# nrfice.net
KiCad netlist of a schematic drawn in EAGLE
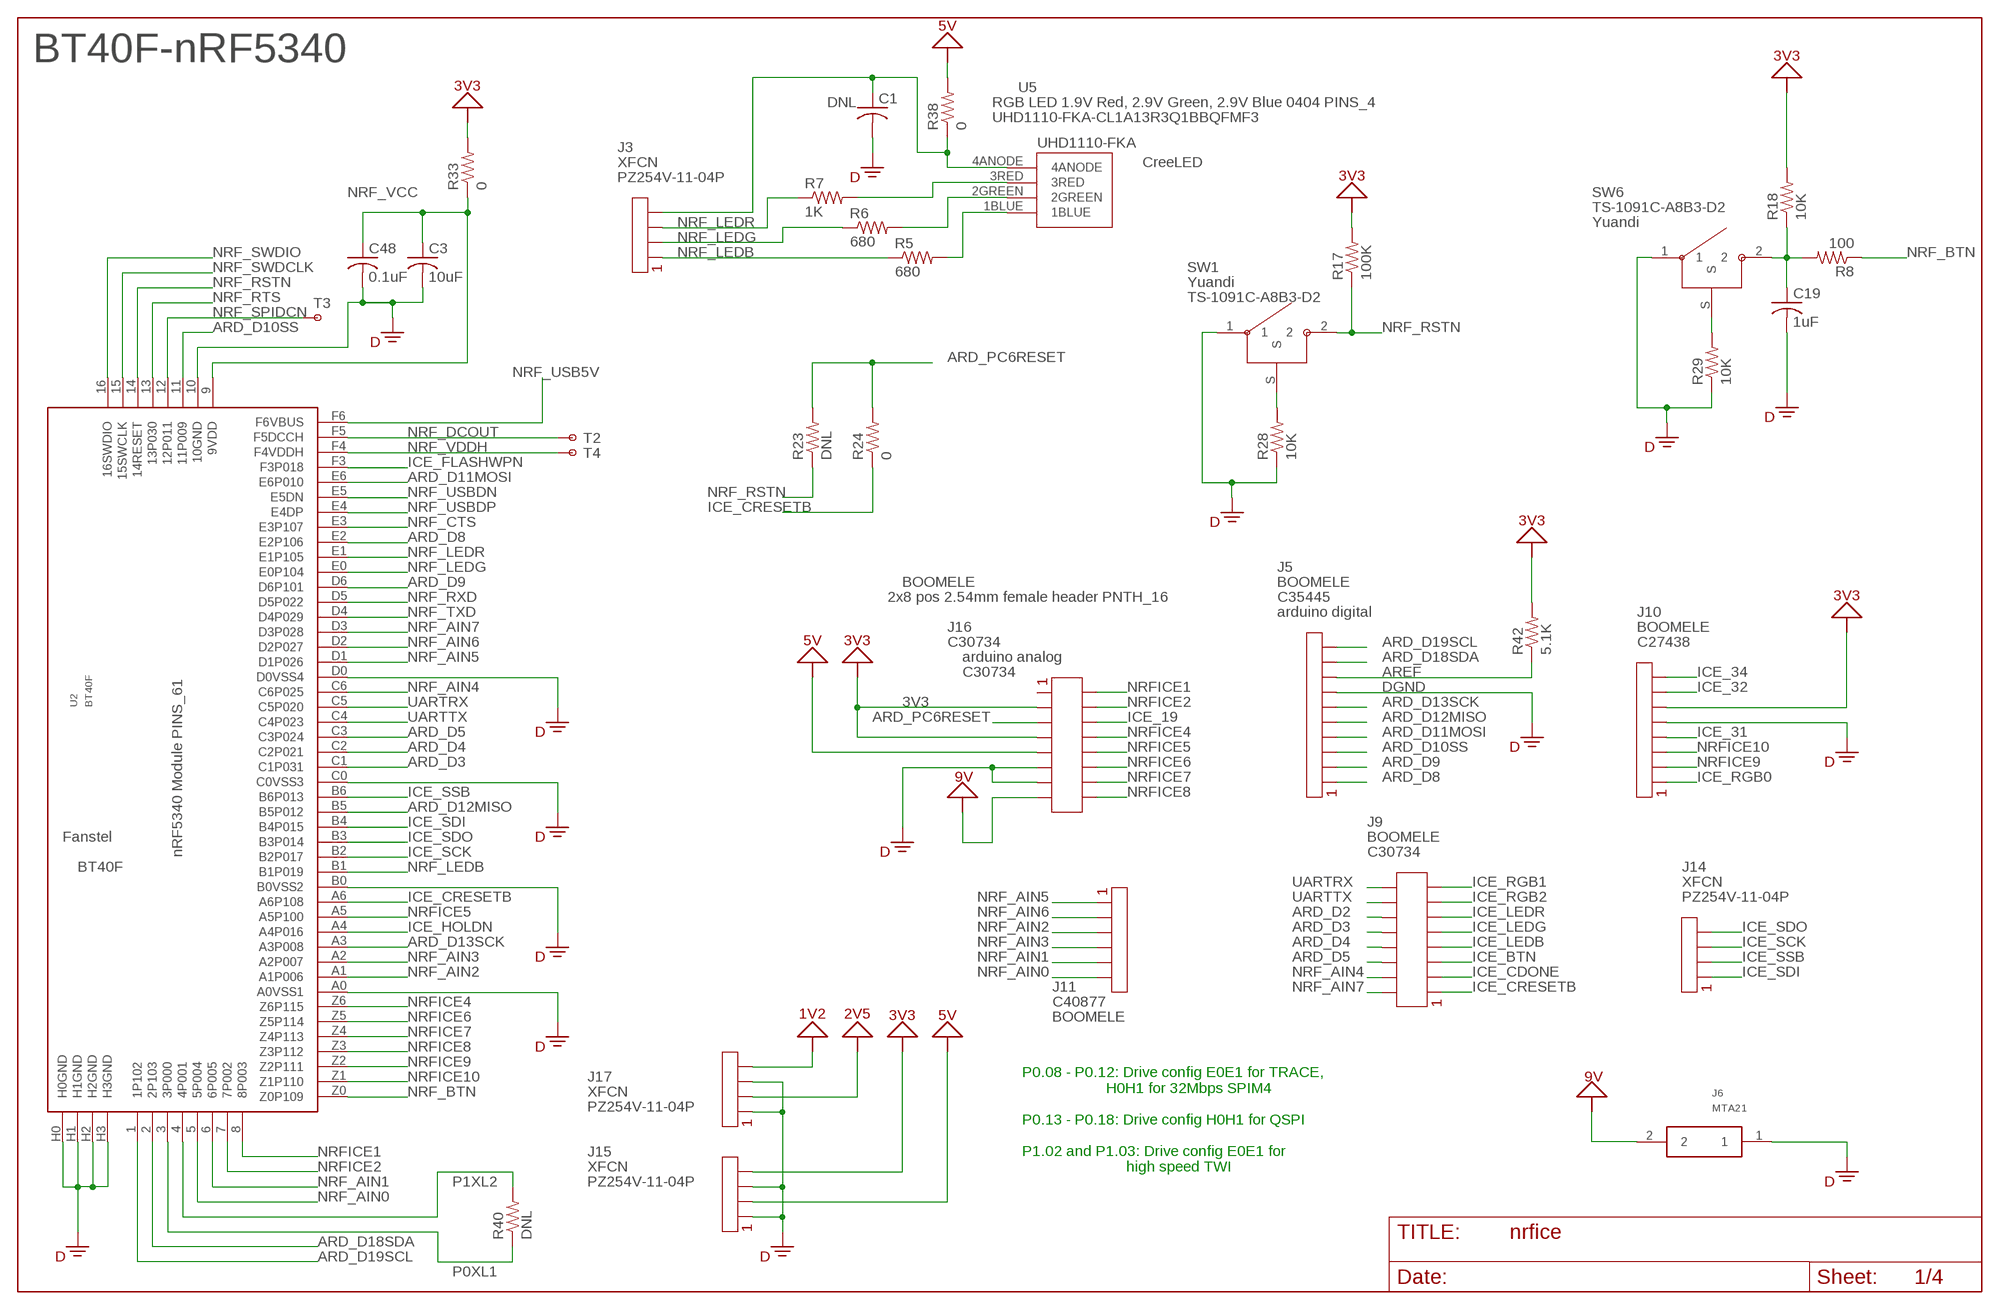
[diagram p0: schematic, sheet 1]
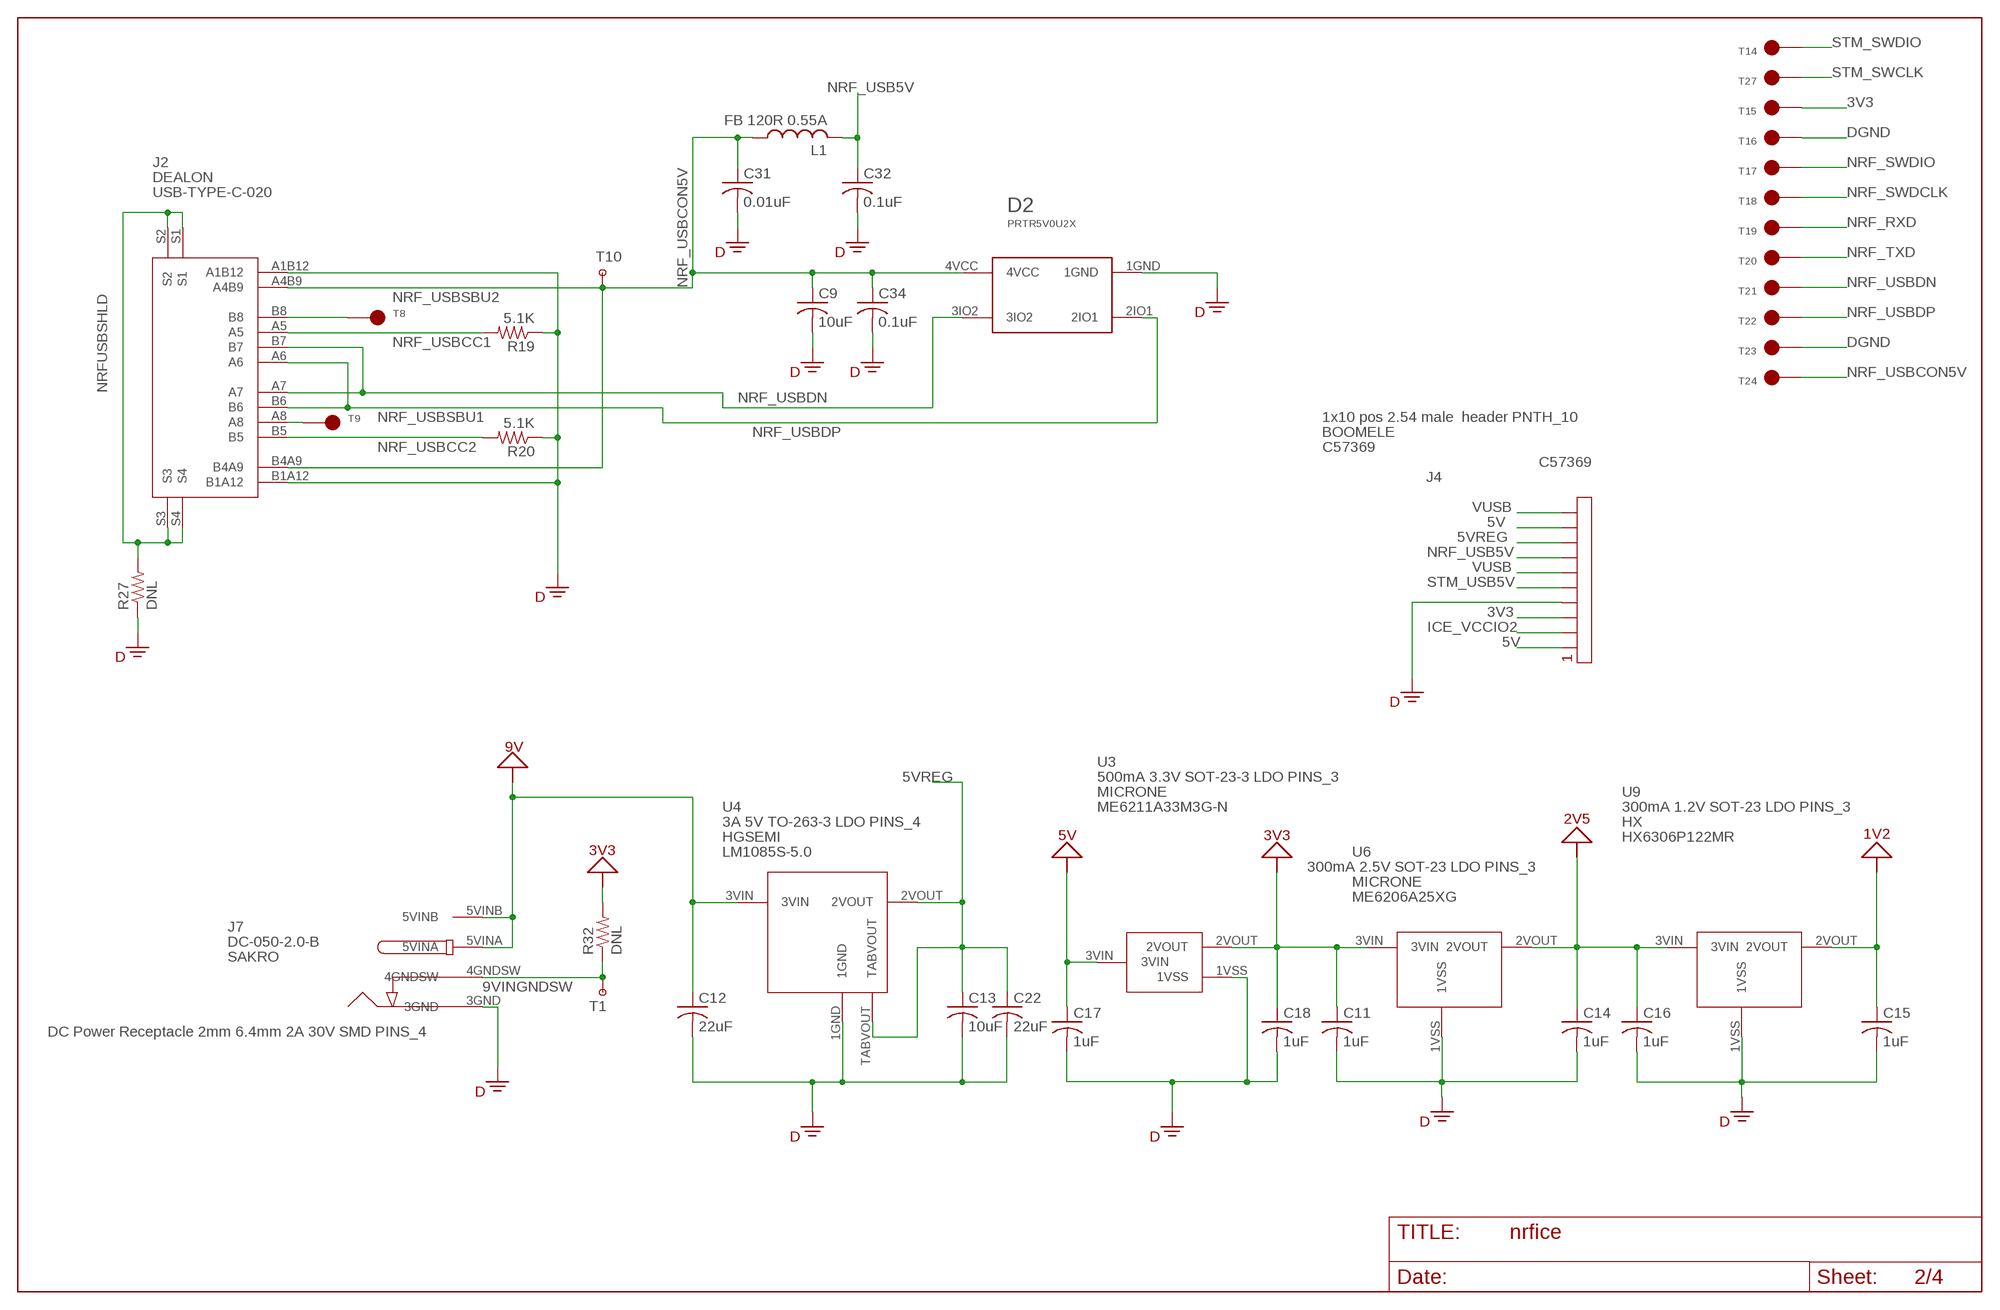
[diagram p1: schematic, sheet 2]
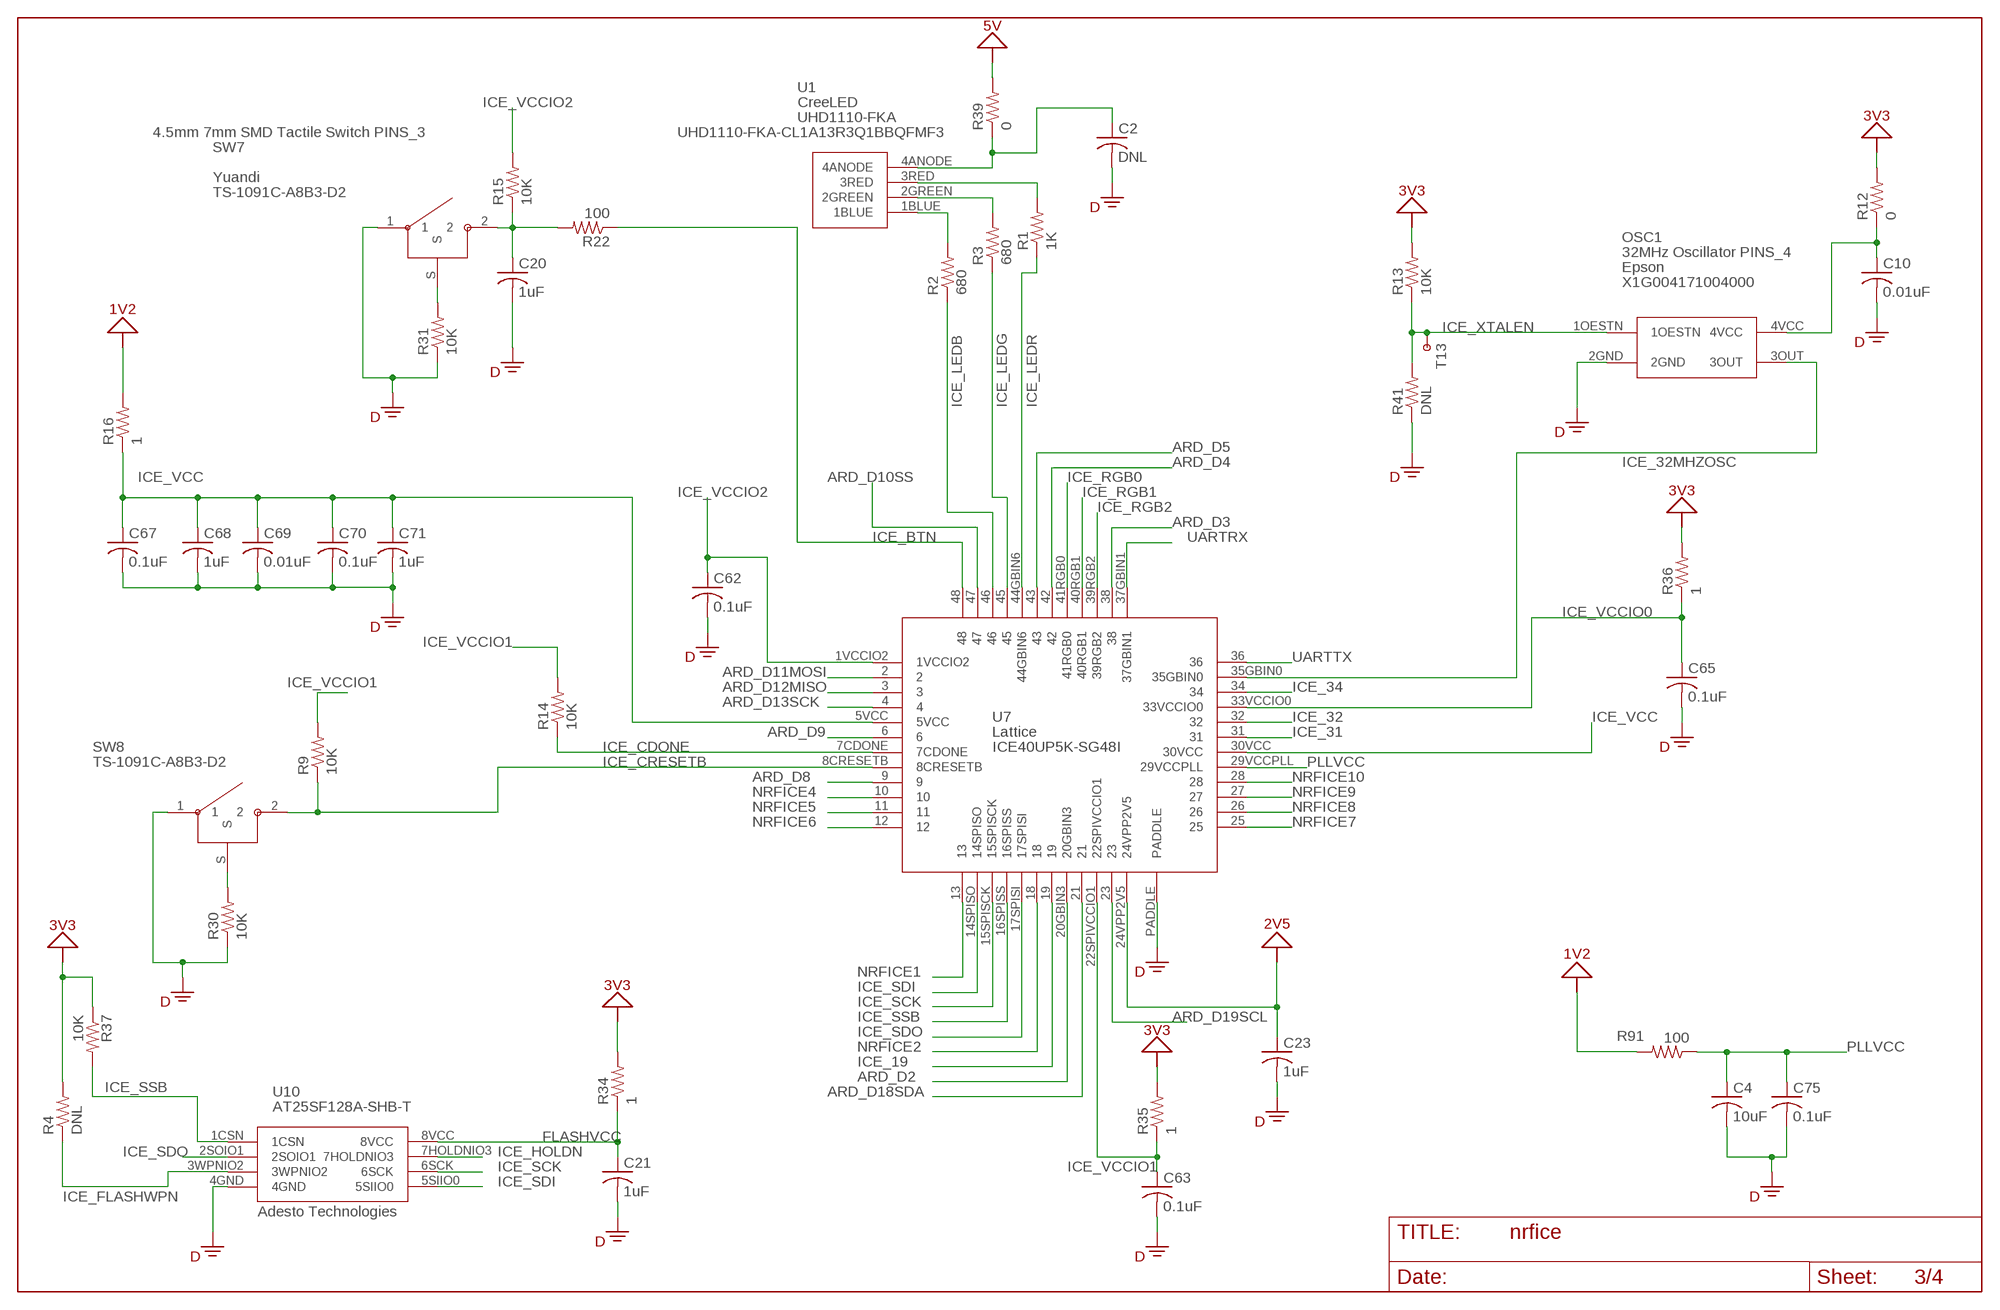
[diagram p2: schematic, sheet 3]
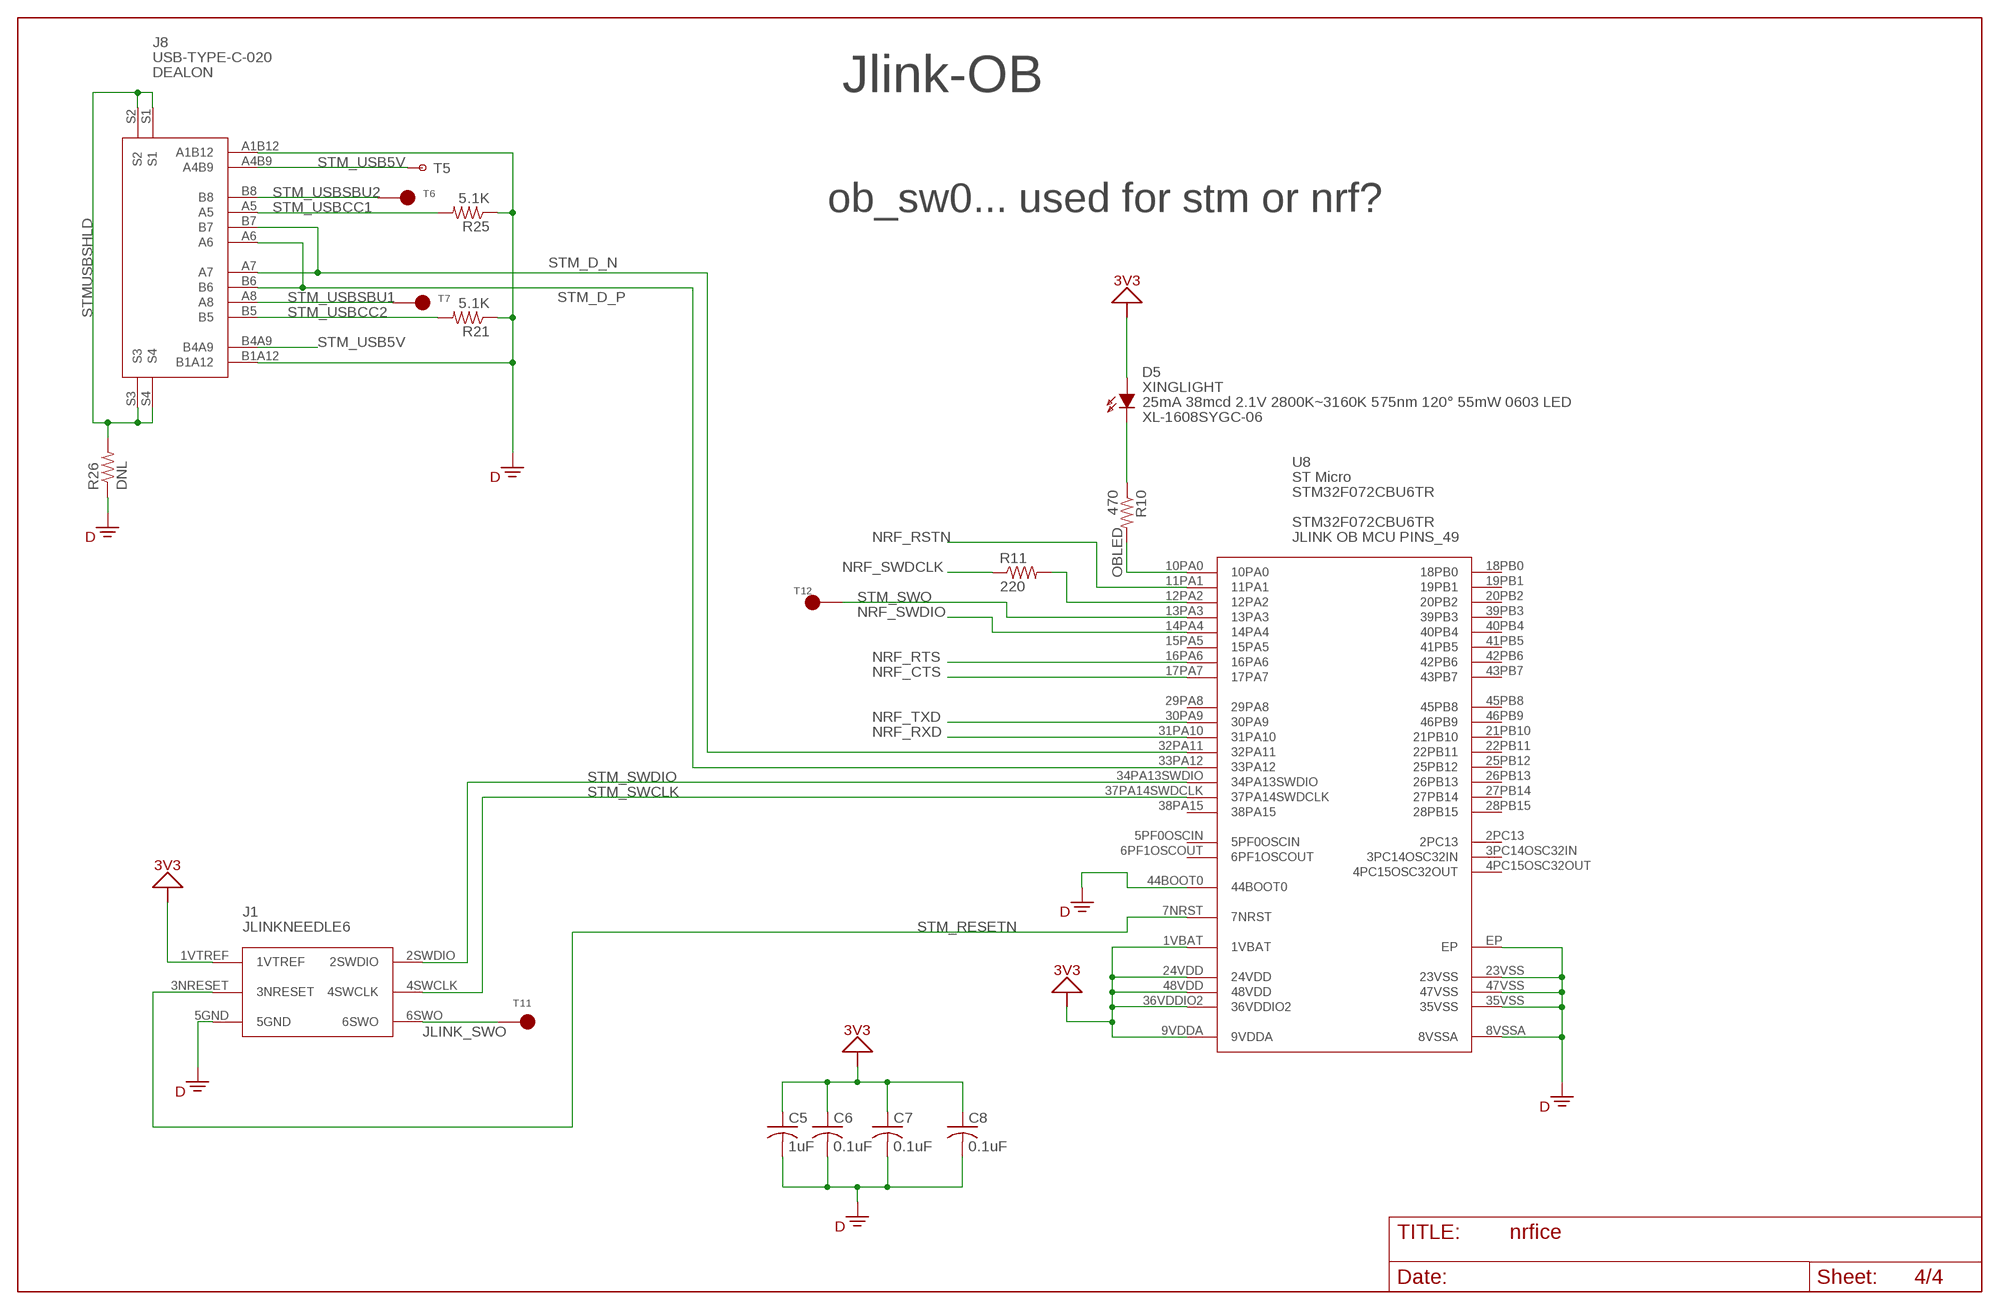
[diagram p3: schematic, sheet 4]

(export (version "E")
  (design (tool "Eeschema 10.0.6"))
  (components
    (comp (ref "C5")
      (value "1uF")
      (footprint "eagle-import:RCL_C0402")
      (fields
        (field (name "DESC") "1uF,10V,10%,X5R,0402")
        (field (name "MAN") "Samsung")
        (field (name "MPN") "CL05A105KP5NNNC")
      )
      (libsource (lib "eagle-import") (part "C-USC0402"))
    )
    (comp (ref "C6")
      (value "0.1uF")
      (footprint "eagle-import:RCL_C0402")
      (fields
        (field (name "DESC") "0.1uF,10V,10%,X7R,0402")
        (field (name "MAN") "KEMET")
        (field (name "MPN") "C0402C104K8RAC7867")
      )
      (libsource (lib "eagle-import") (part "C-USC0402"))
    )
    (comp (ref "C7")
      (value "0.1uF")
      (footprint "eagle-import:RCL_C0402")
      (fields
        (field (name "DESC") "0.1uF,10V,10%,X7R,0402")
        (field (name "MAN") "KEMET")
        (field (name "MPN") "C0402C104K8RAC7867")
      )
      (libsource (lib "eagle-import") (part "C-USC0402"))
    )
    (comp (ref "C8")
      (value "0.1uF")
      (footprint "eagle-import:RCL_C0402")
      (fields
        (field (name "DESC") "0.1uF,10V,10%,X7R,0402")
        (field (name "MAN") "KEMET")
        (field (name "MPN") "C0402C104K8RAC7867")
      )
      (libsource (lib "eagle-import") (part "C-USC0402"))
    )
    (comp (ref "D5")
      (value "XL-1608SYGC-06")
      (footprint "eagle-import:XL-1608SYGC-06")
      (fields
        (field (name "DESC") "25mA 38mcd 2.1V 2800K~3160K 575nm 120° 55mW 0603 LED")
        (field (name "MAN") "XINGLIGHT")
        (field (name "MPN") "XL-1608SYGC-06")
      )
      (libsource (lib "eagle-import") (part "XL-1608SYGC-06"))
    )
    (comp (ref "J1")
      (value "JLINKNEEDLE6")
      (footprint "eagle-import:JLINKNEEDLE6")
      (fields (field (name "DESC") "DNL"))
      (libsource (lib "eagle-import") (part "JLINKNEEDLE6"))
    )
    (comp (ref "J8")
      (value "USB-TYPE-C-020")
      (footprint "eagle-import:USB-TYPE-C-020")
      (fields
        (field (name "DESC") "usb type c connector PINS_12")
        (field (name "MAN") "DEALON")
        (field (name "MPN") "USB-TYPE-C-020")
      )
      (libsource (lib "eagle-import") (part "USB-TYPE-C-020"))
    )
    (comp (ref "R10")
      (value "470")
      (footprint "eagle-import:RCL_R0402")
      (fields
        (field (name "DESC") "470 Ohm,1%,1/16W,0402")
        (field (name "MAN") "YAGEO")
        (field (name "MPN") "RC0402FR-07470RL")
      )
      (libsource (lib "eagle-import") (part "R-US_R0402"))
    )
    (comp (ref "R11")
      (value "220")
      (footprint "eagle-import:RCL_R0402")
      (fields
        (field (name "DESC") "220 Ohm,1%,1/16W,0402")
        (field (name "MAN") "YAGEO")
        (field (name "MPN") "RC0402FR-07220RL")
      )
      (libsource (lib "eagle-import") (part "R-US_R0402"))
    )
    (comp (ref "R21")
      (value "5.1K")
      (footprint "eagle-import:RCL_R0402")
      (fields (field (name "MPN") "RC0402FR-075K1L"))
      (libsource (lib "eagle-import") (part "R-US_R0402"))
    )
    (comp (ref "R25")
      (value "5.1K")
      (footprint "eagle-import:RCL_R0402")
      (fields (field (name "MPN") "RC0402FR-075K1L"))
      (libsource (lib "eagle-import") (part "R-US_R0402"))
    )
    (comp (ref "R26")
      (value "DNL")
      (footprint "eagle-import:RCL_R0402")
      (fields (field (name "DESC") "DNL") (field (name "MAN") "YAGEO") (field (name "MPN") "RC0402FR-0710KL"))
      (libsource (lib "eagle-import") (part "R-US_R0402"))
    )
    (comp (ref "T5")
      (value "MTA1")
      (footprint "eagle-import:MTA1")
      (fields (field (name "DESC") "DNL"))
      (libsource (lib "eagle-import") (part "MTA1"))
    )
    (comp (ref "T6")
      (value "T")
      (footprint "eagle-import:T")
      (fields (field (name "DESC") "DNL"))
      (libsource (lib "eagle-import") (part "T"))
    )
    (comp (ref "T7")
      (value "T")
      (footprint "eagle-import:T")
      (fields (field (name "DESC") "DNL"))
      (libsource (lib "eagle-import") (part "T"))
    )
    (comp (ref "T11")
      (value "T")
      (footprint "eagle-import:T")
      (fields (field (name "DESC") "DNL"))
      (libsource (lib "eagle-import") (part "T"))
    )
    (comp (ref "T12")
      (value "T")
      (footprint "eagle-import:T")
      (fields (field (name "DESC") "DNL"))
      (libsource (lib "eagle-import") (part "T"))
    )
    (comp (ref "U8")
      (value "STM32F072CBU6TR")
      (footprint "eagle-import:STM32F072CBU6TR")
      (fields
        (field (name "DESC") "JLINK OB MCU PINS_49")
        (field (name "MAN") "ST Micro")
        (field (name "MPN") "STM32F072CBU6TR")
      )
      (libsource (lib "eagle-import") (part "STM32F072CBU6TR"))
    )
    (comp (ref "C9")
      (value "10uF")
      (footprint "eagle-import:RCL_C0805")
      (fields
        (field (name "DESC") "10uF,16V,10%,X5R,0805")
        (field (name "MAN") "Samsung")
        (field (name "MPN") "CL21A106KOQNNNE")
      )
      (libsource (lib "eagle-import") (part "C-USC0805"))
    )
    (comp (ref "C11")
      (value "1uF")
      (footprint "eagle-import:RCL_C0402")
      (fields
        (field (name "DESC") "1uF,10V,10%,X5R,0402")
        (field (name "MAN") "Samsung")
        (field (name "MPN") "CL05A105KP5NNNC")
      )
      (libsource (lib "eagle-import") (part "C-USC0402"))
    )
    (comp (ref "C12")
      (value "22uF")
      (footprint "eagle-import:RCL_C0805")
      (fields
        (field (name "DESC") "22uF,25V,20%,X5R,0805")
        (field (name "MAN") "Samsung")
        (field (name "MPN") "CL21A226MAYNNNE")
      )
      (libsource (lib "eagle-import") (part "C-USC0805"))
    )
    (comp (ref "C13")
      (value "10uF")
      (footprint "eagle-import:RCL_C0805")
      (fields
        (field (name "DESC") "10uF,16V,10%,X5R,0805")
        (field (name "MAN") "Samsung")
        (field (name "MPN") "CL21A106KOQNNNE")
      )
      (libsource (lib "eagle-import") (part "C-USC0805"))
    )
    (comp (ref "C14")
      (value "1uF")
      (footprint "eagle-import:RCL_C0402")
      (fields
        (field (name "DESC") "1uF,10V,10%,X5R,0402")
        (field (name "MAN") "Samsung")
        (field (name "MPN") "CL05A105KP5NNNC")
      )
      (libsource (lib "eagle-import") (part "C-USC0402"))
    )
    (comp (ref "C15")
      (value "1uF")
      (footprint "eagle-import:RCL_C0402")
      (fields
        (field (name "DESC") "1uF,10V,10%,X5R,0402")
        (field (name "MAN") "Samsung")
        (field (name "MPN") "CL05A105KP5NNNC")
      )
      (libsource (lib "eagle-import") (part "C-USC0402"))
    )
    (comp (ref "C16")
      (value "1uF")
      (footprint "eagle-import:RCL_C0402")
      (fields
        (field (name "DESC") "1uF,10V,10%,X5R,0402")
        (field (name "MAN") "Samsung")
        (field (name "MPN") "CL05A105KP5NNNC")
      )
      (libsource (lib "eagle-import") (part "C-USC0402"))
    )
    (comp (ref "C17")
      (value "1uF")
      (footprint "eagle-import:RCL_C0402")
      (fields
        (field (name "DESC") "1uF,10V,10%,X5R,0402")
        (field (name "MAN") "Samsung")
        (field (name "MPN") "CL05A105KP5NNNC")
      )
      (libsource (lib "eagle-import") (part "C-USC0402"))
    )
    (comp (ref "C18")
      (value "1uF")
      (footprint "eagle-import:RCL_C0402")
      (fields
        (field (name "DESC") "1uF,10V,10%,X5R,0402")
        (field (name "MAN") "Samsung")
        (field (name "MPN") "CL05A105KP5NNNC")
      )
      (libsource (lib "eagle-import") (part "C-USC0402"))
    )
    (comp (ref "C22")
      (value "22uF")
      (footprint "eagle-import:RCL_C0805")
      (fields
        (field (name "DESC") "22uF,25V,20%,X5R,0805")
        (field (name "MAN") "Samsung")
        (field (name "MPN") "CL21A226MAYNNNE")
      )
      (libsource (lib "eagle-import") (part "C-USC0805"))
    )
    (comp (ref "C31")
      (value "0.01uF")
      (footprint "eagle-import:RCL_C0402")
      (fields (field (name "MPN") "C0402C103J4RAC"))
      (libsource (lib "eagle-import") (part "C-USC0402"))
    )
    (comp (ref "C32")
      (value "0.1uF")
      (footprint "eagle-import:RCL_C0402")
      (fields (field (name "MPN") "C0402C104K8RAC7867"))
      (libsource (lib "eagle-import") (part "C-USC0402"))
    )
    (comp (ref "C34")
      (value "0.1uF")
      (footprint "eagle-import:RCL_C0402")
      (fields (field (name "MPN") "C0402C104K8RAC7867"))
      (libsource (lib "eagle-import") (part "C-USC0402"))
    )
    (comp (ref "D2")
      (value "PRTR5V0U2X")
      (footprint "eagle-import:PRTR5V0U2X")
      (fields (field (name "MAN") "Nexperia") (field (name "MPN") "PRTR5V0U2X"))
      (libsource (lib "eagle-import") (part "PRTR5V0U2X"))
    )
    (comp (ref "J2")
      (value "USB-TYPE-C-020")
      (footprint "eagle-import:USB-TYPE-C-020")
      (fields
        (field (name "DESC") "usb type c connector PINS_12")
        (field (name "MAN") "DEALON")
        (field (name "MPN") "USB-TYPE-C-020")
      )
      (libsource (lib "eagle-import") (part "USB-TYPE-C-020"))
    )
    (comp (ref "J4")
      (value "C57369")
      (footprint "eagle-import:C57369")
      (fields
        (field (name "DESC") "1x10 pos 2.54 male  header PNTH_10")
        (field (name "MAN") "BOOMELE")
        (field (name "MPN") "C57369")
      )
      (libsource (lib "eagle-import") (part "C57369"))
    )
    (comp (ref "J7")
      (value "DC-050-2.0-B")
      (footprint "eagle-import:DC-050-2.0-B")
      (fields
        (field (name "DESC") "DC Power Receptacle 2mm 6.4mm 2A 30V SMD PINS_4")
        (field (name "MAN") "SAKRO")
        (field (name "MPN") "DC-050-2.0-B")
      )
      (libsource (lib "eagle-import") (part "DC-050-2.0-B"))
    )
    (comp (ref "L1")
      (value "FB 120R 0.55A")
      (footprint "eagle-import:L0402")
      (fields (field (name "MPN") "BLM15AG121SN1D"))
      (libsource (lib "eagle-import") (part "L-USL0402"))
    )
    (comp (ref "R19")
      (value "5.1K")
      (footprint "eagle-import:RCL_R0402")
      (fields (field (name "MPN") "RC0402FR-075K1L"))
      (libsource (lib "eagle-import") (part "R-US_R0402"))
    )
    (comp (ref "R20")
      (value "5.1K")
      (footprint "eagle-import:RCL_R0402")
      (fields (field (name "MPN") "RC0402FR-075K1L"))
      (libsource (lib "eagle-import") (part "R-US_R0402"))
    )
    (comp (ref "R27")
      (value "DNL")
      (footprint "eagle-import:RCL_R0402")
      (fields (field (name "MPN") "RC0402FR-0710KL"))
      (libsource (lib "eagle-import") (part "R-US_R0402"))
    )
    (comp (ref "R32")
      (value "DNL")
      (footprint "eagle-import:RCL_R0402")
      (fields (field (name "MPN") "RC0402FR-0710KL"))
      (libsource (lib "eagle-import") (part "R-US_R0402"))
    )
    (comp (ref "T1")
      (value "MTA1")
      (footprint "eagle-import:MTA1")
      (fields (field (name "DESC") "DNL"))
      (libsource (lib "eagle-import") (part "MTA1"))
    )
    (comp (ref "T8")
      (value "T")
      (footprint "eagle-import:T")
      (fields (field (name "DESC") "DNL"))
      (libsource (lib "eagle-import") (part "T"))
    )
    (comp (ref "T9")
      (value "T")
      (footprint "eagle-import:T")
      (fields (field (name "DESC") "DNL"))
      (libsource (lib "eagle-import") (part "T"))
    )
    (comp (ref "T10")
      (value "MTA1")
      (footprint "eagle-import:MTA1")
      (fields (field (name "DESC") "DNL"))
      (libsource (lib "eagle-import") (part "MTA1"))
    )
    (comp (ref "T14")
      (value "TT2")
      (footprint "eagle-import:T2")
      (libsource (lib "eagle-import") (part "TT2"))
    )
    (comp (ref "T15")
      (value "TT2")
      (footprint "eagle-import:T2")
      (libsource (lib "eagle-import") (part "TT2"))
    )
    (comp (ref "T16")
      (value "TT2")
      (footprint "eagle-import:T2")
      (libsource (lib "eagle-import") (part "TT2"))
    )
    (comp (ref "T17")
      (value "TT2")
      (footprint "eagle-import:T2")
      (libsource (lib "eagle-import") (part "TT2"))
    )
    (comp (ref "T18")
      (value "TT2")
      (footprint "eagle-import:T2")
      (libsource (lib "eagle-import") (part "TT2"))
    )
    (comp (ref "T19")
      (value "TT2")
      (footprint "eagle-import:T2")
      (libsource (lib "eagle-import") (part "TT2"))
    )
    (comp (ref "T20")
      (value "TT2")
      (footprint "eagle-import:T2")
      (libsource (lib "eagle-import") (part "TT2"))
    )
    (comp (ref "T21")
      (value "TT2")
      (footprint "eagle-import:T2")
      (libsource (lib "eagle-import") (part "TT2"))
    )
    (comp (ref "T22")
      (value "TT2")
      (footprint "eagle-import:T2")
      (libsource (lib "eagle-import") (part "TT2"))
    )
    (comp (ref "T23")
      (value "TT2")
      (footprint "eagle-import:T2")
      (libsource (lib "eagle-import") (part "TT2"))
    )
    (comp (ref "T24")
      (value "TT2")
      (footprint "eagle-import:T2")
      (libsource (lib "eagle-import") (part "TT2"))
    )
    (comp (ref "T27")
      (value "TT2")
      (footprint "eagle-import:T2")
      (libsource (lib "eagle-import") (part "TT2"))
    )
    (comp (ref "U3")
      (value "ME6211A33M3G-N")
      (footprint "eagle-import:ME6211A33M3G-N")
      (fields
        (field (name "DESC") "500mA 3.3V SOT-23-3 LDO PINS_3")
        (field (name "MAN") "MICRONE")
        (field (name "MPN") "ME6211A33M3G-N")
      )
      (libsource (lib "eagle-import") (part "ME6211A33M3G-N"))
    )
    (comp (ref "U4")
      (value "LM1085S-5.0")
      (footprint "eagle-import:LM1085S-5.0")
      (fields
        (field (name "DESC") "3A 5V TO-263-3 LDO PINS_4")
        (field (name "MAN") "HGSEMI")
        (field (name "MPN") "LM1085S-5.0")
      )
      (libsource (lib "eagle-import") (part "LM1085S-5.0"))
    )
    (comp (ref "U6")
      (value "ME6206A25XG")
      (footprint "eagle-import:ME6206A25XG")
      (fields
        (field (name "DESC") "300mA 2.5V SOT-23 LDO PINS_3")
        (field (name "MAN") "MICRONE")
        (field (name "MPN") "ME6206A25XG")
      )
      (libsource (lib "eagle-import") (part "ME6206A25XG"))
    )
    (comp (ref "U9")
      (value "HX6306P122MR")
      (footprint "eagle-import:HX6306P122MR")
      (fields
        (field (name "DESC") "300mA 1.2V SOT-23 LDO PINS_3")
        (field (name "MAN") "HX")
        (field (name "MPN") "HX6306P122MR")
      )
      (libsource (lib "eagle-import") (part "HX6306P122MR"))
    )
    (comp (ref "C2")
      (value "DNL")
      (footprint "eagle-import:RCL_C0402")
      (fields (field (name "MPN") "CL05A105KP5NNNC"))
      (libsource (lib "eagle-import") (part "C-USC0402"))
    )
    (comp (ref "C4")
      (value "10uF")
      (footprint "eagle-import:RCL_C0805")
      (fields
        (field (name "DESC") "10uF,16V,10%,X5R,0805")
        (field (name "MAN") "Samsung")
        (field (name "MPN") "CL21A106KOQNNNE")
      )
      (libsource (lib "eagle-import") (part "C-USC0805"))
    )
    (comp (ref "C10")
      (value "0.01uF")
      (footprint "eagle-import:RCL_C0402")
      (fields
        (field (name "DESC") "0.01uF,16V,5%,X7R,0402")
        (field (name "MAN") "KEMET")
        (field (name "MPN") "C0402C103J4RAC")
      )
      (libsource (lib "eagle-import") (part "C-USC0402"))
    )
    (comp (ref "C20")
      (value "1uF")
      (footprint "eagle-import:RCL_C0402")
      (fields (field (name "MPN") "CL05A105KP5NNNC"))
      (libsource (lib "eagle-import") (part "C-USC0402"))
    )
    (comp (ref "C21")
      (value "1uF")
      (footprint "eagle-import:RCL_C0402")
      (fields (field (name "MPN") "CL05A105KP5NNNC"))
      (libsource (lib "eagle-import") (part "C-USC0402"))
    )
    (comp (ref "C23")
      (value "1uF")
      (footprint "eagle-import:RCL_C0402")
      (fields
        (field (name "DESC") "1uF,10V,10%,X5R,0402")
        (field (name "MAN") "Samsung")
        (field (name "MPN") "CL05A105KP5NNNC")
      )
      (libsource (lib "eagle-import") (part "C-USC0402"))
    )
    (comp (ref "C62")
      (value "0.1uF")
      (footprint "eagle-import:RCL_C0402")
      (fields
        (field (name "DESC") "0.1uF,10V,10%,X7R,0402")
        (field (name "MAN") "KEMET")
        (field (name "MPN") "C0402C104K8RAC7867")
      )
      (libsource (lib "eagle-import") (part "C-USC0402"))
    )
    (comp (ref "C63")
      (value "0.1uF")
      (footprint "eagle-import:RCL_C0402")
      (fields
        (field (name "DESC") "0.1uF,10V,10%,X7R,0402")
        (field (name "MAN") "KEMET")
        (field (name "MPN") "C0402C104K8RAC7867")
      )
      (libsource (lib "eagle-import") (part "C-USC0402"))
    )
    (comp (ref "C65")
      (value "0.1uF")
      (footprint "eagle-import:RCL_C0402")
      (fields
        (field (name "DESC") "0.1uF,10V,10%,X7R,0402")
        (field (name "MAN") "KEMET")
        (field (name "MPN") "C0402C104K8RAC7867")
      )
      (libsource (lib "eagle-import") (part "C-USC0402"))
    )
    (comp (ref "C67")
      (value "0.1uF")
      (footprint "eagle-import:RCL_C0402")
      (fields
        (field (name "DESC") "0.1uF,10V,10%,X7R,0402")
        (field (name "MAN") "KEMET")
        (field (name "MPN") "C0402C104K8RAC7867")
      )
      (libsource (lib "eagle-import") (part "C-USC0402"))
    )
    (comp (ref "C68")
      (value "1uF")
      (footprint "eagle-import:RCL_C0402")
      (fields
        (field (name "DESC") "1uF,10V,10%,X5R,0402")
        (field (name "MAN") "Samsung")
        (field (name "MPN") "CL05A105KP5NNNC")
      )
      (libsource (lib "eagle-import") (part "C-USC0402"))
    )
    (comp (ref "C69")
      (value "0.01uF")
      (footprint "eagle-import:RCL_C0402")
      (fields
        (field (name "DESC") "0.01uF,16V,5%,X7R,0402")
        (field (name "MAN") "KEMET")
        (field (name "MPN") "C0402C103J4RAC")
      )
      (libsource (lib "eagle-import") (part "C-USC0402"))
    )
    (comp (ref "C70")
      (value "0.1uF")
      (footprint "eagle-import:RCL_C0402")
      (fields
        (field (name "DESC") "0.1uF,10V,10%,X7R,0402")
        (field (name "MAN") "KEMET")
        (field (name "MPN") "C0402C104K8RAC7867")
      )
      (libsource (lib "eagle-import") (part "C-USC0402"))
    )
    (comp (ref "C71")
      (value "1uF")
      (footprint "eagle-import:RCL_C0402")
      (fields
        (field (name "DESC") "1uF,10V,10%,X5R,0402")
        (field (name "MAN") "Samsung")
        (field (name "MPN") "CL05A105KP5NNNC")
      )
      (libsource (lib "eagle-import") (part "C-USC0402"))
    )
    (comp (ref "C75")
      (value "0.1uF")
      (footprint "eagle-import:RCL_C0402")
      (fields
        (field (name "DESC") "0.1uF,10V,10%,X7R,0402")
        (field (name "MAN") "KEMET")
        (field (name "MPN") "C0402C104K8RAC7867")
      )
      (libsource (lib "eagle-import") (part "C-USC0402"))
    )
    (comp (ref "OSC1")
      (value "X1G004171004000")
      (footprint "eagle-import:X1G004171004000")
      (fields
        (field (name "DESC") "32MHz Oscillator PINS_4")
        (field (name "MAN") "Epson")
        (field (name "MPN") "X1G004171004000")
      )
      (libsource (lib "eagle-import") (part "X1G004171004000"))
    )
    (comp (ref "R1")
      (value "1K")
      (footprint "eagle-import:RCL_R0402")
      (fields (field (name "MPN") "RC0402FR-071KL"))
      (libsource (lib "eagle-import") (part "R-US_R0402"))
    )
    (comp (ref "R2")
      (value "680")
      (footprint "eagle-import:RCL_R0402")
      (fields (field (name "MPN") "RC0402FR-07680RL"))
      (libsource (lib "eagle-import") (part "R-US_R0402"))
    )
    (comp (ref "R3")
      (value "680")
      (footprint "eagle-import:RCL_R0402")
      (fields (field (name "MPN") "RC0402FR-07680RL"))
      (libsource (lib "eagle-import") (part "R-US_R0402"))
    )
    (comp (ref "R4")
      (value "DNL")
      (footprint "eagle-import:RCL_R0402")
      (fields (field (name "DESC") "DNL") (field (name "MAN") "YAGEO") (field (name "MPN") "RC0402FR-0710KL"))
      (libsource (lib "eagle-import") (part "R-US_R0402"))
    )
    (comp (ref "R9")
      (value "10K")
      (footprint "eagle-import:RCL_R0402")
      (fields
        (field (name "DESC") "10K Ohm,1%,1/16W,0402")
        (field (name "MAN") "YAGEO")
        (field (name "MPN") "RC0402FR-0710KL")
      )
      (libsource (lib "eagle-import") (part "R-US_R0402"))
    )
    (comp (ref "R12")
      (value "0")
      (footprint "eagle-import:RCL_R0603")
      (fields
        (field (name "DESC") "0 Ohm,1%,1/10W,0603")
        (field (name "MAN") "YAGEO")
        (field (name "MPN") "RC0603FR-070RL")
      )
      (libsource (lib "eagle-import") (part "R-US_R0603"))
    )
    (comp (ref "R13")
      (value "10K")
      (footprint "eagle-import:RCL_R0402")
      (fields
        (field (name "DESC") "10K Ohm,1%,1/16W,0402")
        (field (name "MAN") "YAGEO")
        (field (name "MPN") "RC0402FR-0710KL")
      )
      (libsource (lib "eagle-import") (part "R-US_R0402"))
    )
    (comp (ref "R14")
      (value "10K")
      (footprint "eagle-import:RCL_R0402")
      (fields
        (field (name "DESC") "10K Ohm,1%,1/16W,0402")
        (field (name "MAN") "YAGEO")
        (field (name "MPN") "RC0402FR-0710KL")
      )
      (libsource (lib "eagle-import") (part "R-US_R0402"))
    )
    (comp (ref "R15")
      (value "10K")
      (footprint "eagle-import:RCL_R0402")
      (fields
        (field (name "DESC") "10K Ohm,1%,1/16W,0402")
        (field (name "MAN") "YAGEO")
        (field (name "MPN") "RC0402FR-0710KL")
      )
      (libsource (lib "eagle-import") (part "R-US_R0402"))
    )
    (comp (ref "R16")
      (value "1")
      (footprint "eagle-import:RCL_R0603")
      (fields
        (field (name "DESC") "1 Ohm,1%,1/10W,0603")
        (field (name "MAN") "YAGEO")
        (field (name "MPN") "RC0603FR-071RL")
      )
      (libsource (lib "eagle-import") (part "R-US_R0603"))
    )
    (comp (ref "R22")
      (value "100")
      (footprint "eagle-import:RCL_R0402")
      (fields
        (field (name "DESC") "100 Ohm,1%,1/16W,0402")
        (field (name "MAN") "YAGEO")
        (field (name "MPN") "RC0402FR-07100RL")
      )
      (libsource (lib "eagle-import") (part "R-US_R0402"))
    )
    (comp (ref "R30")
      (value "10K")
      (footprint "eagle-import:RCL_R0402")
      (fields
        (field (name "DESC") "10K Ohm,1%,1/16W,0402")
        (field (name "MAN") "YAGEO")
        (field (name "MPN") "RC0402FR-0710KL")
      )
      (libsource (lib "eagle-import") (part "R-US_R0402"))
    )
    (comp (ref "R31")
      (value "10K")
      (footprint "eagle-import:RCL_R0402")
      (fields
        (field (name "DESC") "10K Ohm,1%,1/16W,0402")
        (field (name "MAN") "YAGEO")
        (field (name "MPN") "RC0402FR-0710KL")
      )
      (libsource (lib "eagle-import") (part "R-US_R0402"))
    )
    (comp (ref "R34")
      (value "1")
      (footprint "eagle-import:RCL_R0603")
      (fields
        (field (name "DESC") "1 Ohm,1%,1/10W,0603")
        (field (name "MAN") "YAGEO")
        (field (name "MPN") "RC0603FR-071RL")
      )
      (libsource (lib "eagle-import") (part "R-US_R0603"))
    )
    (comp (ref "R35")
      (value "1")
      (footprint "eagle-import:RCL_R0603")
      (fields
        (field (name "DESC") "1 Ohm,1%,1/10W,0603")
        (field (name "MAN") "YAGEO")
        (field (name "MPN") "RC0603FR-071RL")
      )
      (libsource (lib "eagle-import") (part "R-US_R0603"))
    )
    (comp (ref "R36")
      (value "1")
      (footprint "eagle-import:RCL_R0603")
      (fields
        (field (name "DESC") "1 Ohm,1%,1/10W,0603")
        (field (name "MAN") "YAGEO")
        (field (name "MPN") "RC0603FR-071RL")
      )
      (libsource (lib "eagle-import") (part "R-US_R0603"))
    )
    (comp (ref "R37")
      (value "10K")
      (footprint "eagle-import:RCL_R0402")
      (fields
        (field (name "DESC") "10K Ohm,1%,1/16W,0402")
        (field (name "MAN") "YAGEO")
        (field (name "MPN") "RC0402FR-0710KL")
      )
      (libsource (lib "eagle-import") (part "R-US_R0402"))
    )
    (comp (ref "R39")
      (value "0")
      (footprint "eagle-import:RCL_R0402")
      (fields
        (field (name "DESC") "0 Ohm,1%,1/16W,0402")
        (field (name "MAN") "YAGEO")
        (field (name "MPN") "RC0402FR-070RL")
      )
      (libsource (lib "eagle-import") (part "R-US_R0402"))
    )
    (comp (ref "R41")
      (value "DNL")
      (footprint "eagle-import:RCL_R0402")
      (fields (field (name "DESC") "DNL") (field (name "MAN") "YAGEO") (field (name "MPN") "RC0402FR-0710KL"))
      (libsource (lib "eagle-import") (part "R-US_R0402"))
    )
    (comp (ref "R91")
      (value "100")
      (footprint "eagle-import:RCL_R0402")
      (fields
        (field (name "DESC") "100 Ohm,1%,1/16W,0402")
        (field (name "MAN") "YAGEO")
        (field (name "MPN") "RC0402FR-07100RL")
      )
      (libsource (lib "eagle-import") (part "R-US_R0402"))
    )
    (comp (ref "SW7")
      (value "TS-1091C-A8B3-D2")
      (footprint "eagle-import:TS-1091C-A8B3-D2")
      (fields
        (field (name "DESC") "4.5mm 7mm SMD Tactile Switch PINS_3")
        (field (name "MAN") "Yuandi")
        (field (name "MPN") "TS-1091C-A8B3-D2")
      )
      (libsource (lib "eagle-import") (part "TS-1091C-A8B3-D2"))
    )
    (comp (ref "SW8")
      (value "TS-1091C-A8B3-D2")
      (footprint "eagle-import:TS-1091C-A8B3-D2")
      (fields
        (field (name "DESC") "4.5mm 7mm SMD Tactile Switch PINS_3")
        (field (name "MAN") "Yuandi")
        (field (name "MPN") "TS-1091C-A8B3-D2")
      )
      (libsource (lib "eagle-import") (part "TS-1091C-A8B3-D2"))
    )
    (comp (ref "T13")
      (value "MTA1")
      (footprint "eagle-import:MTA1")
      (fields (field (name "DESC") "DNL"))
      (libsource (lib "eagle-import") (part "MTA1"))
    )
    (comp (ref "U1")
      (value "UHD1110-FKA")
      (footprint "eagle-import:UHD1110-FKA")
      (fields
        (field (name "DESC") "RGB LED 1.9V Red, 2.9V Green, 2.9V Blue 0404 PINS_4")
        (field (name "MAN") "CreeLED")
        (field (name "MPN") "UHD1110-FKA-CL1A13R3Q1BBQFMF3")
      )
      (libsource (lib "eagle-import") (part "UHD1110-FKA"))
    )
    (comp (ref "U7")
      (value "ICE40UP5K-SG48I")
      (footprint "eagle-import:ICE40UP5K-SG48I")
      (fields
        (field (name "DESC") "FPGA 48-VFQFN PINS_48")
        (field (name "MAN") "Lattice")
        (field (name "MPN") "ICE40UP5K-SG48I")
      )
      (libsource (lib "eagle-import") (part "ICE40UP5K-SG48I"))
    )
    (comp (ref "U10")
      (value "AT25SF128A-SHB-T")
      (footprint "eagle-import:AT25SF128A-SHB-T")
      (fields
        (field (name "DESC") "NOR Flash 128 Mbit,2.7V to 3.6V,SOIC-W 208mil PINS_8")
        (field (name "MAN") "Adesto Technologies")
        (field (name "MPN") "AT25SF128A-SHB-T")
      )
      (libsource (lib "eagle-import") (part "AT25SF128A-SHB-T"))
    )
    (comp (ref "C1")
      (value "DNL")
      (footprint "eagle-import:RCL_C0402")
      (fields (field (name "DESC") "DNL") (field (name "MPN") "CL05A105KP5NNNC"))
      (libsource (lib "eagle-import") (part "C-USC0402"))
    )
    (comp (ref "C3")
      (value "10uF")
      (footprint "eagle-import:RCL_C0805")
      (fields
        (field (name "DESC") "10uF,16V,10%,X5R,0805")
        (field (name "MAN") "Samsung")
        (field (name "MPN") "CL21A106KOQNNNE")
      )
      (libsource (lib "eagle-import") (part "C-USC0805"))
    )
    (comp (ref "C19")
      (value "1uF")
      (footprint "eagle-import:RCL_C0402")
      (fields (field (name "MPN") "CL05A105KP5NNNC"))
      (libsource (lib "eagle-import") (part "C-USC0402"))
    )
    (comp (ref "C48")
      (value "0.1uF")
      (footprint "eagle-import:RCL_C0402")
      (fields (field (name "MPN") "C0402C104K8RAC7867"))
      (libsource (lib "eagle-import") (part "C-USC0402"))
    )
    (comp (ref "J3")
      (value "PZ254V-11-04P")
      (footprint "eagle-import:PZ254V-11-04P")
      (fields
        (field (name "DESC") "1x4 pos 2.54 male  header PNTH_4")
        (field (name "MAN") "XFCN")
        (field (name "MPN") "PZ254V-11-04P")
      )
      (libsource (lib "eagle-import") (part "PZ254V-11-04P"))
    )
    (comp (ref "J5")
      (value "C35445")
      (footprint "eagle-import:C35445")
      (fields
        (field (name "DESC") "1x10 pos 2.54 female header PNTH_10")
        (field (name "MAN") "BOOMELE")
        (field (name "MPN") "C35445")
      )
      (libsource (lib "eagle-import") (part "C35445"))
    )
    (comp (ref "J6")
      (value "MTA21")
      (footprint "eagle-import:MTA21")
      (libsource (lib "eagle-import") (part "MTA21"))
    )
    (comp (ref "J9")
      (value "C30734")
      (footprint "eagle-import:C30734")
      (fields
        (field (name "DESC") "2x8 pos 2.54mm female header PNTH_16")
        (field (name "MAN") "BOOMELE")
        (field (name "MPN") "C30734")
      )
      (libsource (lib "eagle-import") (part "C30734"))
    )
    (comp (ref "J10")
      (value "C27438")
      (footprint "eagle-import:C27438")
      (fields (field (name "DESC") "DNL") (field (name "MAN") "BOOMELE") (field (name "MPN") "C27438"))
      (libsource (lib "eagle-import") (part "C27438"))
    )
    (comp (ref "J11")
      (value "C40877")
      (footprint "eagle-import:C40877")
      (fields
        (field (name "DESC") "1x6 pos 2.54 female header PNTH_6")
        (field (name "MAN") "BOOMELE")
        (field (name "MPN") "C40877")
      )
      (libsource (lib "eagle-import") (part "C40877"))
    )
    (comp (ref "J14")
      (value "PZ254V-11-04P")
      (footprint "eagle-import:PZ254V-11-04P")
      (fields
        (field (name "DESC") "1x4 pos 2.54 male  header PNTH_4")
        (field (name "MAN") "XFCN")
        (field (name "MPN") "PZ254V-11-04P")
      )
      (libsource (lib "eagle-import") (part "PZ254V-11-04P"))
    )
    (comp (ref "J15")
      (value "PZ254V-11-04P")
      (footprint "eagle-import:PZ254V-11-04P")
      (fields
        (field (name "DESC") "1x4 pos 2.54 male  header PNTH_4")
        (field (name "MAN") "XFCN")
        (field (name "MPN") "PZ254V-11-04P")
      )
      (libsource (lib "eagle-import") (part "PZ254V-11-04P"))
    )
    (comp (ref "J16")
      (value "C30734")
      (footprint "eagle-import:C30734")
      (fields
        (field (name "DESC") "2x8 pos 2.54mm female header PNTH_16")
        (field (name "MAN") "BOOMELE")
        (field (name "MPN") "C30734")
      )
      (libsource (lib "eagle-import") (part "C30734"))
    )
    (comp (ref "J17")
      (value "PZ254V-11-04P")
      (footprint "eagle-import:PZ254V-11-04P")
      (fields
        (field (name "DESC") "1x4 pos 2.54 male  header PNTH_4")
        (field (name "MAN") "XFCN")
        (field (name "MPN") "PZ254V-11-04P")
      )
      (libsource (lib "eagle-import") (part "PZ254V-11-04P"))
    )
    (comp (ref "R5")
      (value "680")
      (footprint "eagle-import:RCL_R0402")
      (fields (field (name "MPN") "RC0402FR-07680RL"))
      (libsource (lib "eagle-import") (part "R-US_R0402"))
    )
    (comp (ref "R6")
      (value "680")
      (footprint "eagle-import:RCL_R0402")
      (fields (field (name "MPN") "RC0402FR-07680RL"))
      (libsource (lib "eagle-import") (part "R-US_R0402"))
    )
    (comp (ref "R7")
      (value "1K")
      (footprint "eagle-import:RCL_R0402")
      (fields (field (name "MPN") "RC0402FR-071KL"))
      (libsource (lib "eagle-import") (part "R-US_R0402"))
    )
    (comp (ref "R8")
      (value "100")
      (footprint "eagle-import:RCL_R0402")
      (fields
        (field (name "DESC") "100 Ohm,1%,1/16W,0402")
        (field (name "MAN") "YAGEO")
        (field (name "MPN") "RC0402FR-07100RL")
      )
      (libsource (lib "eagle-import") (part "R-US_R0402"))
    )
    (comp (ref "R17")
      (value "100K")
      (footprint "eagle-import:RCL_R0402")
      (fields
        (field (name "DESC") "100K Ohm,1%,1/16W,0402")
        (field (name "MAN") "YAGEO")
        (field (name "MPN") "RC0402FR-07100KL")
      )
      (libsource (lib "eagle-import") (part "R-US_R0402"))
    )
    (comp (ref "R18")
      (value "10K")
      (footprint "eagle-import:RCL_R0402")
      (fields
        (field (name "DESC") "10K Ohm,1%,1/16W,0402")
        (field (name "MAN") "YAGEO")
        (field (name "MPN") "RC0402FR-0710KL")
      )
      (libsource (lib "eagle-import") (part "R-US_R0402"))
    )
    (comp (ref "R23")
      (value "DNL")
      (footprint "eagle-import:RCL_R0402")
      (fields (field (name "DESC") "DNL") (field (name "MAN") "YAGEO") (field (name "MPN") "RC0402FR-0710KL"))
      (libsource (lib "eagle-import") (part "R-US_R0402"))
    )
    (comp (ref "R24")
      (value "0")
      (footprint "eagle-import:RCL_R0402")
      (fields
        (field (name "DESC") "0 Ohm,1%,1/16W,0402")
        (field (name "MAN") "YAGEO")
        (field (name "MPN") "RC0402FR-070RL")
      )
      (libsource (lib "eagle-import") (part "R-US_R0402"))
    )
    (comp (ref "R28")
      (value "10K")
      (footprint "eagle-import:RCL_R0402")
      (fields
        (field (name "DESC") "10K Ohm,1%,1/16W,0402")
        (field (name "MAN") "YAGEO")
        (field (name "MPN") "RC0402FR-0710KL")
      )
      (libsource (lib "eagle-import") (part "R-US_R0402"))
    )
    (comp (ref "R29")
      (value "10K")
      (footprint "eagle-import:RCL_R0402")
      (fields
        (field (name "DESC") "10K Ohm,1%,1/16W,0402")
        (field (name "MAN") "YAGEO")
        (field (name "MPN") "RC0402FR-0710KL")
      )
      (libsource (lib "eagle-import") (part "R-US_R0402"))
    )
    (comp (ref "R33")
      (value "0")
      (footprint "eagle-import:RCL_R0603")
      (fields
        (field (name "DESC") "0 Ohm,1%,1/10W,0603")
        (field (name "MAN") "YAGEO")
        (field (name "MPN") "RC0603FR-070RL")
      )
      (libsource (lib "eagle-import") (part "R-US_R0603"))
    )
    (comp (ref "R38")
      (value "0")
      (footprint "eagle-import:RCL_R0402")
      (fields (field (name "MPN") "RC0402FR-070RL"))
      (libsource (lib "eagle-import") (part "R-US_R0402"))
    )
    (comp (ref "R40")
      (value "DNL")
      (footprint "eagle-import:RCL_R0402")
      (fields (field (name "MPN") "RC0402FR-0710KL"))
      (libsource (lib "eagle-import") (part "R-US_R0402"))
    )
    (comp (ref "R42")
      (value "5.1K")
      (footprint "eagle-import:RCL_R0402")
      (fields
        (field (name "DESC") "5.1K Ohm,1%,1/16W,0402")
        (field (name "MAN") "YAGEO")
        (field (name "MPN") "RC0402FR-075K1L")
      )
      (libsource (lib "eagle-import") (part "R-US_R0402"))
    )
    (comp (ref "SW1")
      (value "TS-1091C-A8B3-D2")
      (footprint "eagle-import:TS-1091C-A8B3-D2")
      (fields
        (field (name "DESC") "4.5mm 7mm SMD Tactile Switch PINS_3")
        (field (name "MAN") "Yuandi")
        (field (name "MPN") "TS-1091C-A8B3-D2")
      )
      (libsource (lib "eagle-import") (part "TS-1091C-A8B3-D2"))
    )
    (comp (ref "SW6")
      (value "TS-1091C-A8B3-D2")
      (footprint "eagle-import:TS-1091C-A8B3-D2")
      (fields
        (field (name "DESC") "4.5mm 7mm SMD Tactile Switch PINS_3")
        (field (name "MAN") "Yuandi")
        (field (name "MPN") "TS-1091C-A8B3-D2")
      )
      (libsource (lib "eagle-import") (part "TS-1091C-A8B3-D2"))
    )
    (comp (ref "T2")
      (value "MTA1")
      (footprint "eagle-import:MTA1")
      (fields (field (name "DESC") "DNL"))
      (libsource (lib "eagle-import") (part "MTA1"))
    )
    (comp (ref "T3")
      (value "MTA1")
      (footprint "eagle-import:MTA1")
      (fields (field (name "DESC") "DNL"))
      (libsource (lib "eagle-import") (part "MTA1"))
    )
    (comp (ref "T4")
      (value "MTA1")
      (footprint "eagle-import:MTA1")
      (fields (field (name "DESC") "DNL"))
      (libsource (lib "eagle-import") (part "MTA1"))
    )
    (comp (ref "U2")
      (value "BT40F")
      (footprint "eagle-import:BT40F")
      (fields
        (field (name "DESC") "nRF5340 Module PINS_61")
        (field (name "MAN") "Fanstel")
        (field (name "MPN") "BT40F")
      )
      (libsource (lib "eagle-import") (part "BT40F"))
    )
    (comp (ref "U5")
      (value "UHD1110-FKA")
      (footprint "eagle-import:UHD1110-FKA")
      (fields
        (field (name "DESC") "RGB LED 1.9V Red, 2.9V Green, 2.9V Blue 0404 PINS_4")
        (field (name "MAN") "CreeLED")
        (field (name "MPN") "UHD1110-FKA-CL1A13R3Q1BBQFMF3")
      )
      (libsource (lib "eagle-import") (part "UHD1110-FKA"))
    )
  )
  (nets
    (net (code "1") (name "1V2") (class "Default")
      (node (ref "C15") (pin "1") (pinfunction "1_1") (pintype "passive"))
      (node (ref "J17") (pin "4") (pinfunction "4_4") (pintype "bidirectional"))
      (node (ref "R16") (pin "2") (pinfunction "2_2") (pintype "passive"))
      (node (ref "R91") (pin "2") (pinfunction "2_2") (pintype "passive"))
      (node (ref "U9") (pin "2VOUT") (pinfunction "2VOUT_2VOUT") (pintype "bidirectional"))
    )
    (net (code "2") (name "2V5") (class "Default")
      (node (ref "C14") (pin "1") (pinfunction "1_1") (pintype "passive"))
      (node (ref "C16") (pin "1") (pinfunction "1_1") (pintype "passive"))
      (node (ref "C23") (pin "1") (pinfunction "1_1") (pintype "passive"))
      (node (ref "J17") (pin "2") (pinfunction "2_2") (pintype "bidirectional"))
      (node (ref "U6") (pin "2VOUT") (pinfunction "2VOUT_2VOUT") (pintype "bidirectional"))
      (node (ref "U7") (pin "24VPP2V5") (pinfunction "24VPP2V5_24VPP2V5") (pintype "bidirectional"))
      (node (ref "U9") (pin "3VIN") (pinfunction "3VIN_3VIN") (pintype "bidirectional"))
    )
    (net (code "3") (name "3V3") (class "Default")
      (node (ref "C11") (pin "1") (pinfunction "1_1") (pintype "passive"))
      (node (ref "C18") (pin "1") (pinfunction "1_1") (pintype "passive"))
      (node (ref "C5") (pin "1") (pinfunction "1_1") (pintype "passive"))
      (node (ref "C6") (pin "1") (pinfunction "1_1") (pintype "passive"))
      (node (ref "C7") (pin "1") (pinfunction "1_1") (pintype "passive"))
      (node (ref "C8") (pin "1") (pinfunction "1_1") (pintype "passive"))
      (node (ref "D5") (pin "A") (pinfunction "A_A") (pintype "passive"))
      (node (ref "J1") (pin "1VTREF") (pinfunction "1VTREF_1VTREF") (pintype "bidirectional"))
      (node (ref "J10") (pin "6") (pinfunction "6_6") (pintype "bidirectional"))
      (node (ref "J15") (pin "4") (pinfunction "4_4") (pintype "bidirectional"))
      (node (ref "J16") (pin "3") (pinfunction "3_3") (pintype "bidirectional"))
      (node (ref "J16") (pin "7") (pinfunction "7_7") (pintype "bidirectional"))
      (node (ref "J4") (pin "3") (pinfunction "3_3") (pintype "bidirectional"))
      (node (ref "R12") (pin "2") (pinfunction "2_2") (pintype "passive"))
      (node (ref "R13") (pin "2") (pinfunction "2_2") (pintype "passive"))
      (node (ref "R17") (pin "2") (pinfunction "2_2") (pintype "passive"))
      (node (ref "R18") (pin "2") (pinfunction "2_2") (pintype "passive"))
      (node (ref "R32") (pin "2") (pinfunction "2_2") (pintype "passive"))
      (node (ref "R33") (pin "2") (pinfunction "2_2") (pintype "passive"))
      (node (ref "R34") (pin "2") (pinfunction "2_2") (pintype "passive"))
      (node (ref "R35") (pin "2") (pinfunction "2_2") (pintype "passive"))
      (node (ref "R36") (pin "2") (pinfunction "2_2") (pintype "passive"))
      (node (ref "R37") (pin "1") (pinfunction "1_1") (pintype "passive"))
      (node (ref "R4") (pin "2") (pinfunction "2_2") (pintype "passive"))
      (node (ref "R42") (pin "2") (pinfunction "2_2") (pintype "passive"))
      (node (ref "T15") (pin "T") (pinfunction "T_T") (pintype "bidirectional"))
      (node (ref "U3") (pin "2VOUT") (pinfunction "2VOUT_2VOUT") (pintype "bidirectional"))
      (node (ref "U6") (pin "3VIN") (pinfunction "3VIN_3VIN") (pintype "bidirectional"))
      (node (ref "U8") (pin "1VBAT") (pinfunction "1VBAT_1VBAT") (pintype "bidirectional"))
      (node (ref "U8") (pin "24VDD") (pinfunction "24VDD_24VDD") (pintype "bidirectional"))
      (node (ref "U8") (pin "36VDDIO2") (pinfunction "36VDDIO2_36VDDIO2") (pintype "bidirectional"))
      (node (ref "U8") (pin "48VDD") (pinfunction "48VDD_48VDD") (pintype "bidirectional"))
      (node (ref "U8") (pin "9VDDA") (pinfunction "9VDDA_9VDDA") (pintype "bidirectional"))
    )
    (net (code "4") (name "5V") (class "Default")
      (node (ref "C17") (pin "1") (pinfunction "1_1") (pintype "passive"))
      (node (ref "J15") (pin "2") (pinfunction "2_2") (pintype "bidirectional"))
      (node (ref "J16") (pin "9") (pinfunction "9_9") (pintype "bidirectional"))
      (node (ref "J4") (pin "1") (pinfunction "1_1") (pintype "bidirectional"))
      (node (ref "J4") (pin "9") (pinfunction "9_9") (pintype "bidirectional"))
      (node (ref "R38") (pin "2") (pinfunction "2_2") (pintype "passive"))
      (node (ref "R39") (pin "2") (pinfunction "2_2") (pintype "passive"))
      (node (ref "U3") (pin "3VIN") (pinfunction "3VIN_3VIN") (pintype "bidirectional"))
    )
    (net (code "5") (name "5VREG") (class "Default")
      (node (ref "C13") (pin "1") (pinfunction "1_1") (pintype "passive"))
      (node (ref "C22") (pin "1") (pinfunction "1_1") (pintype "passive"))
      (node (ref "J4") (pin "8") (pinfunction "8_8") (pintype "bidirectional"))
      (node (ref "U4") (pin "2VOUT") (pinfunction "2VOUT_2VOUT") (pintype "bidirectional"))
      (node (ref "U4") (pin "TABVOUT") (pinfunction "TABVOUT_TABVOUT") (pintype "bidirectional"))
    )
    (net (code "6") (name "9V") (class "Default")
      (node (ref "C12") (pin "1") (pinfunction "1_1") (pintype "passive"))
      (node (ref "J16") (pin "15") (pinfunction "15_15") (pintype "bidirectional"))
      (node (ref "J6") (pin "2") (pinfunction "2_2") (pintype "bidirectional"))
      (node (ref "J7") (pin "5VINA") (pinfunction "5VINA_5VINA") (pintype "bidirectional"))
      (node (ref "J7") (pin "5VINB") (pinfunction "5VINB_5VINB") (pintype "bidirectional"))
      (node (ref "U4") (pin "3VIN") (pinfunction "3VIN_3VIN") (pintype "bidirectional"))
    )
    (net (code "7") (name "9VINGNDSW") (class "Default")
      (node (ref "J7") (pin "4GNDSW") (pinfunction "4GNDSW_4GNDSW") (pintype "bidirectional"))
      (node (ref "R32") (pin "1") (pinfunction "1_1") (pintype "passive"))
      (node (ref "T1") (pin "1") (pinfunction "1_1") (pintype "bidirectional"))
    )
    (net (code "8") (name "ARD_D2") (class "Default")
      (node (ref "J9") (pin "12") (pinfunction "12_12") (pintype "bidirectional"))
      (node (ref "U7") (pin "20GBIN3") (pinfunction "20GBIN3_20GBIN3") (pintype "bidirectional"))
    )
    (net (code "9") (name "ARD_D3") (class "Default")
      (node (ref "J9") (pin "10") (pinfunction "10_10") (pintype "bidirectional"))
      (node (ref "U2") (pin "C1") (pinfunction "C1P031_C1") (pintype "bidirectional"))
      (node (ref "U7") (pin "38") (pinfunction "38_38") (pintype "bidirectional"))
    )
    (net (code "10") (name "ARD_D4") (class "Default")
      (node (ref "J9") (pin "8") (pinfunction "8_8") (pintype "bidirectional"))
      (node (ref "U2") (pin "C2") (pinfunction "C2P021_C2") (pintype "bidirectional"))
      (node (ref "U7") (pin "42") (pinfunction "42_42") (pintype "bidirectional"))
    )
    (net (code "11") (name "ARD_D5") (class "Default")
      (node (ref "J9") (pin "6") (pinfunction "6_6") (pintype "bidirectional"))
      (node (ref "U2") (pin "C3") (pinfunction "C3P024_C3") (pintype "bidirectional"))
      (node (ref "U7") (pin "43") (pinfunction "43_43") (pintype "bidirectional"))
    )
    (net (code "12") (name "ARD_D8") (class "Default")
      (node (ref "J5") (pin "1") (pinfunction "1_1") (pintype "bidirectional"))
      (node (ref "U2") (pin "E2") (pinfunction "E2P106_E2") (pintype "bidirectional"))
      (node (ref "U7") (pin "9") (pinfunction "9_9") (pintype "bidirectional"))
    )
    (net (code "13") (name "ARD_D9") (class "Default")
      (node (ref "J5") (pin "2") (pinfunction "2_2") (pintype "bidirectional"))
      (node (ref "U2") (pin "D6") (pinfunction "D6P101_D6") (pintype "bidirectional"))
      (node (ref "U7") (pin "6") (pinfunction "6_6") (pintype "bidirectional"))
    )
    (net (code "14") (name "ARD_D10SS") (class "Default")
      (node (ref "J5") (pin "3") (pinfunction "3_3") (pintype "bidirectional"))
      (node (ref "U2") (pin "11") (pinfunction "11P009_11") (pintype "bidirectional"))
      (node (ref "U7") (pin "47") (pinfunction "47_47") (pintype "bidirectional"))
    )
    (net (code "15") (name "ARD_D11MOSI") (class "Default")
      (node (ref "J5") (pin "4") (pinfunction "4_4") (pintype "bidirectional"))
      (node (ref "U2") (pin "E6") (pinfunction "E6P010_E6") (pintype "bidirectional"))
      (node (ref "U7") (pin "2") (pinfunction "2_2") (pintype "bidirectional"))
    )
    (net (code "16") (name "ARD_D12MISO") (class "Default")
      (node (ref "J5") (pin "5") (pinfunction "5_5") (pintype "bidirectional"))
      (node (ref "U2") (pin "B5") (pinfunction "B5P012_B5") (pintype "bidirectional"))
      (node (ref "U7") (pin "3") (pinfunction "3_3") (pintype "bidirectional"))
    )
    (net (code "17") (name "ARD_D13SCK") (class "Default")
      (node (ref "J5") (pin "6") (pinfunction "6_6") (pintype "bidirectional"))
      (node (ref "U2") (pin "A3") (pinfunction "A3P008_A3") (pintype "bidirectional"))
      (node (ref "U7") (pin "4") (pinfunction "4_4") (pintype "bidirectional"))
    )
    (net (code "18") (name "ARD_D18SDA") (class "Default")
      (node (ref "J5") (pin "9") (pinfunction "9_9") (pintype "bidirectional"))
      (node (ref "U2") (pin "2") (pinfunction "2P103_2") (pintype "bidirectional"))
      (node (ref "U7") (pin "21") (pinfunction "21_21") (pintype "bidirectional"))
    )
    (net (code "19") (name "ARD_D19SCL") (class "Default")
      (node (ref "J5") (pin "10") (pinfunction "10_10") (pintype "bidirectional"))
      (node (ref "U2") (pin "1") (pinfunction "1P102_1") (pintype "bidirectional"))
      (node (ref "U7") (pin "23") (pinfunction "23_23") (pintype "bidirectional"))
    )
    (net (code "20") (name "ARD_PC6RESET") (class "Default")
      (node (ref "J16") (pin "5") (pinfunction "5_5") (pintype "bidirectional"))
      (node (ref "R23") (pin "2") (pinfunction "2_2") (pintype "passive"))
      (node (ref "R24") (pin "2") (pinfunction "2_2") (pintype "passive"))
    )
    (net (code "21") (name "AREF") (class "Default")
      (node (ref "J5") (pin "8") (pinfunction "8_8") (pintype "bidirectional"))
      (node (ref "R42") (pin "1") (pinfunction "1_1") (pintype "passive"))
    )
    (net (code "22") (name "DGND") (class "Default")
      (node (ref "C1") (pin "2") (pinfunction "2_2") (pintype "passive"))
      (node (ref "C10") (pin "2") (pinfunction "2_2") (pintype "passive"))
      (node (ref "C11") (pin "2") (pinfunction "2_2") (pintype "passive"))
      (node (ref "C12") (pin "2") (pinfunction "2_2") (pintype "passive"))
      (node (ref "C13") (pin "2") (pinfunction "2_2") (pintype "passive"))
      (node (ref "C14") (pin "2") (pinfunction "2_2") (pintype "passive"))
      (node (ref "C15") (pin "2") (pinfunction "2_2") (pintype "passive"))
      (node (ref "C16") (pin "2") (pinfunction "2_2") (pintype "passive"))
      (node (ref "C17") (pin "2") (pinfunction "2_2") (pintype "passive"))
      (node (ref "C18") (pin "2") (pinfunction "2_2") (pintype "passive"))
      (node (ref "C19") (pin "2") (pinfunction "2_2") (pintype "passive"))
      (node (ref "C2") (pin "2") (pinfunction "2_2") (pintype "passive"))
      (node (ref "C20") (pin "2") (pinfunction "2_2") (pintype "passive"))
      (node (ref "C21") (pin "2") (pinfunction "2_2") (pintype "passive"))
      (node (ref "C22") (pin "2") (pinfunction "2_2") (pintype "passive"))
      (node (ref "C23") (pin "2") (pinfunction "2_2") (pintype "passive"))
      (node (ref "C3") (pin "2") (pinfunction "2_2") (pintype "passive"))
      (node (ref "C31") (pin "2") (pinfunction "2_2") (pintype "passive"))
      (node (ref "C32") (pin "2") (pinfunction "2_2") (pintype "passive"))
      (node (ref "C34") (pin "2") (pinfunction "2_2") (pintype "passive"))
      (node (ref "C4") (pin "2") (pinfunction "2_2") (pintype "passive"))
      (node (ref "C48") (pin "2") (pinfunction "2_2") (pintype "passive"))
      (node (ref "C5") (pin "2") (pinfunction "2_2") (pintype "passive"))
      (node (ref "C6") (pin "2") (pinfunction "2_2") (pintype "passive"))
      (node (ref "C62") (pin "2") (pinfunction "2_2") (pintype "passive"))
      (node (ref "C63") (pin "2") (pinfunction "2_2") (pintype "passive"))
      (node (ref "C65") (pin "2") (pinfunction "2_2") (pintype "passive"))
      (node (ref "C67") (pin "2") (pinfunction "2_2") (pintype "passive"))
      (node (ref "C68") (pin "2") (pinfunction "2_2") (pintype "passive"))
      (node (ref "C69") (pin "2") (pinfunction "2_2") (pintype "passive"))
      (node (ref "C7") (pin "2") (pinfunction "2_2") (pintype "passive"))
      (node (ref "C70") (pin "2") (pinfunction "2_2") (pintype "passive"))
      (node (ref "C71") (pin "2") (pinfunction "2_2") (pintype "passive"))
      (node (ref "C75") (pin "2") (pinfunction "2_2") (pintype "passive"))
      (node (ref "C8") (pin "2") (pinfunction "2_2") (pintype "passive"))
      (node (ref "C9") (pin "2") (pinfunction "2_2") (pintype "passive"))
      (node (ref "D2") (pin "1GND") (pinfunction "1GND_1GND") (pintype "bidirectional"))
      (node (ref "J1") (pin "5GND") (pinfunction "5GND_5GND") (pintype "bidirectional"))
      (node (ref "J10") (pin "5") (pinfunction "5_5") (pintype "bidirectional"))
      (node (ref "J15") (pin "1") (pinfunction "1_1") (pintype "bidirectional"))
      (node (ref "J15") (pin "3") (pinfunction "3_3") (pintype "bidirectional"))
      (node (ref "J16") (pin "11") (pinfunction "11_11") (pintype "bidirectional"))
      (node (ref "J16") (pin "13") (pinfunction "13_13") (pintype "bidirectional"))
      (node (ref "J17") (pin "1") (pinfunction "1_1") (pintype "bidirectional"))
      (node (ref "J17") (pin "3") (pinfunction "3_3") (pintype "bidirectional"))
      (node (ref "J2") (pin "A1B12") (pinfunction "A1B12_A1B12") (pintype "bidirectional"))
      (node (ref "J2") (pin "B1A12") (pinfunction "B1A12_B1A12") (pintype "bidirectional"))
      (node (ref "J4") (pin "4") (pinfunction "4_4") (pintype "bidirectional"))
      (node (ref "J5") (pin "7") (pinfunction "7_7") (pintype "bidirectional"))
      (node (ref "J6") (pin "1") (pinfunction "1_1") (pintype "bidirectional"))
      (node (ref "J7") (pin "3GND") (pinfunction "3GND_3GND") (pintype "bidirectional"))
      (node (ref "J8") (pin "A1B12") (pinfunction "A1B12_A1B12") (pintype "bidirectional"))
      (node (ref "J8") (pin "B1A12") (pinfunction "B1A12_B1A12") (pintype "bidirectional"))
      (node (ref "OSC1") (pin "2GND") (pinfunction "2GND_2GND") (pintype "bidirectional"))
      (node (ref "R19") (pin "1") (pinfunction "1_1") (pintype "passive"))
      (node (ref "R20") (pin "1") (pinfunction "1_1") (pintype "passive"))
      (node (ref "R21") (pin "1") (pinfunction "1_1") (pintype "passive"))
      (node (ref "R25") (pin "1") (pinfunction "1_1") (pintype "passive"))
      (node (ref "R26") (pin "1") (pinfunction "1_1") (pintype "passive"))
      (node (ref "R27") (pin "1") (pinfunction "1_1") (pintype "passive"))
      (node (ref "R28") (pin "1") (pinfunction "1_1") (pintype "passive"))
      (node (ref "R29") (pin "1") (pinfunction "1_1") (pintype "passive"))
      (node (ref "R30") (pin "1") (pinfunction "1_1") (pintype "passive"))
      (node (ref "R31") (pin "1") (pinfunction "1_1") (pintype "passive"))
      (node (ref "R41") (pin "1") (pinfunction "1_1") (pintype "passive"))
      (node (ref "SW1") (pin "1") (pinfunction "1_1") (pintype "bidirectional"))
      (node (ref "SW6") (pin "1") (pinfunction "1_1") (pintype "bidirectional"))
      (node (ref "SW7") (pin "1") (pinfunction "1_1") (pintype "bidirectional"))
      (node (ref "SW8") (pin "1") (pinfunction "1_1") (pintype "bidirectional"))
      (node (ref "T16") (pin "T") (pinfunction "T_T") (pintype "bidirectional"))
      (node (ref "T23") (pin "T") (pinfunction "T_T") (pintype "bidirectional"))
      (node (ref "U10") (pin "4GND") (pinfunction "4GND_4GND") (pintype "bidirectional"))
      (node (ref "U2") (pin "10") (pinfunction "10GND_10") (pintype "bidirectional"))
      (node (ref "U2") (pin "A0") (pinfunction "A0VSS1_A0") (pintype "bidirectional"))
      (node (ref "U2") (pin "B0") (pinfunction "B0VSS2_B0") (pintype "bidirectional"))
      (node (ref "U2") (pin "C0") (pinfunction "C0VSS3_C0") (pintype "bidirectional"))
      (node (ref "U2") (pin "D0") (pinfunction "D0VSS4_D0") (pintype "bidirectional"))
      (node (ref "U2") (pin "H0") (pinfunction "H0GND_H0") (pintype "bidirectional"))
      (node (ref "U2") (pin "H1") (pinfunction "H1GND_H1") (pintype "bidirectional"))
      (node (ref "U2") (pin "H2") (pinfunction "H2GND_H2") (pintype "bidirectional"))
      (node (ref "U2") (pin "H3") (pinfunction "H3GND_H3") (pintype "bidirectional"))
      (node (ref "U3") (pin "1VSS") (pinfunction "1VSS_1VSS") (pintype "bidirectional"))
      (node (ref "U4") (pin "1GND") (pinfunction "1GND_1GND") (pintype "bidirectional"))
      (node (ref "U6") (pin "1VSS") (pinfunction "1VSS_1VSS") (pintype "bidirectional"))
      (node (ref "U7") (pin "PADDLE") (pinfunction "PADDLE_PADDLE") (pintype "bidirectional"))
      (node (ref "U8") (pin "23VSS") (pinfunction "23VSS_23VSS") (pintype "bidirectional"))
      (node (ref "U8") (pin "35VSS") (pinfunction "35VSS_35VSS") (pintype "bidirectional"))
      (node (ref "U8") (pin "44BOOT0") (pinfunction "44BOOT0_44BOOT0") (pintype "bidirectional"))
      (node (ref "U8") (pin "47VSS") (pinfunction "47VSS_47VSS") (pintype "bidirectional"))
      (node (ref "U8") (pin "8VSSA") (pinfunction "8VSSA_8VSSA") (pintype "bidirectional"))
      (node (ref "U8") (pin "EP") (pinfunction "EP_EP") (pintype "bidirectional"))
      (node (ref "U9") (pin "1VSS") (pinfunction "1VSS_1VSS") (pintype "bidirectional"))
    )
    (net (code "23") (name "FLASHVCC") (class "Default")
      (node (ref "C21") (pin "1") (pinfunction "1_1") (pintype "passive"))
      (node (ref "R34") (pin "1") (pinfunction "1_1") (pintype "passive"))
      (node (ref "U10") (pin "8VCC") (pinfunction "8VCC_8VCC") (pintype "bidirectional"))
    )
    (net (code "24") (name "ICE_19") (class "Default")
      (node (ref "J16") (pin "6") (pinfunction "6_6") (pintype "bidirectional"))
      (node (ref "U7") (pin "19") (pinfunction "19_19") (pintype "bidirectional"))
    )
    (net (code "25") (name "ICE_31") (class "Default")
      (node (ref "J10") (pin "4") (pinfunction "4_4") (pintype "bidirectional"))
      (node (ref "U7") (pin "31") (pinfunction "31_31") (pintype "bidirectional"))
    )
    (net (code "26") (name "ICE_32") (class "Default")
      (node (ref "J10") (pin "7") (pinfunction "7_7") (pintype "bidirectional"))
      (node (ref "U7") (pin "32") (pinfunction "32_32") (pintype "bidirectional"))
    )
    (net (code "27") (name "ICE_32MHZOSC") (class "Default")
      (node (ref "OSC1") (pin "3OUT") (pinfunction "3OUT_3OUT") (pintype "bidirectional"))
      (node (ref "U7") (pin "35GBIN0") (pinfunction "35GBIN0_35GBIN0") (pintype "bidirectional"))
    )
    (net (code "28") (name "ICE_34") (class "Default")
      (node (ref "J10") (pin "8") (pinfunction "8_8") (pintype "bidirectional"))
      (node (ref "U7") (pin "34") (pinfunction "34_34") (pintype "bidirectional"))
    )
    (net (code "29") (name "ICE_BTN") (class "Default")
      (node (ref "J9") (pin "5") (pinfunction "5_5") (pintype "bidirectional"))
      (node (ref "R22") (pin "1") (pinfunction "1_1") (pintype "passive"))
      (node (ref "U7") (pin "48") (pinfunction "48_48") (pintype "bidirectional"))
    )
    (net (code "30") (name "ICE_CDONE") (class "Default")
      (node (ref "J9") (pin "3") (pinfunction "3_3") (pintype "bidirectional"))
      (node (ref "R14") (pin "1") (pinfunction "1_1") (pintype "passive"))
      (node (ref "U7") (pin "7CDONE") (pinfunction "7CDONE_7CDONE") (pintype "bidirectional"))
    )
    (net (code "31") (name "ICE_CRESETB") (class "Default")
      (node (ref "J9") (pin "1") (pinfunction "1_1") (pintype "bidirectional"))
      (node (ref "R24") (pin "1") (pinfunction "1_1") (pintype "passive"))
      (node (ref "R9") (pin "1") (pinfunction "1_1") (pintype "passive"))
      (node (ref "SW8") (pin "2") (pinfunction "2_2") (pintype "bidirectional"))
      (node (ref "U2") (pin "A6") (pinfunction "A6P108_A6") (pintype "bidirectional"))
      (node (ref "U7") (pin "8CRESETB") (pinfunction "8CRESETB_8CRESETB") (pintype "bidirectional"))
    )
    (net (code "32") (name "ICE_FLASHWPN") (class "Default")
      (node (ref "R4") (pin "1") (pinfunction "1_1") (pintype "passive"))
      (node (ref "U10") (pin "3WPNIO2") (pinfunction "3WPNIO2_3WPNIO2") (pintype "bidirectional"))
      (node (ref "U2") (pin "F3") (pinfunction "F3P018_F3") (pintype "bidirectional"))
    )
    (net (code "33") (name "ICE_HOLDN") (class "Default")
      (node (ref "U10") (pin "7HOLDNIO3") (pinfunction "7HOLDNIO3_7HOLDNIO3") (pintype "bidirectional"))
      (node (ref "U2") (pin "A4") (pinfunction "A4P016_A4") (pintype "bidirectional"))
    )
    (net (code "34") (name "ICE_LEDB") (class "Default")
      (node (ref "J9") (pin "7") (pinfunction "7_7") (pintype "bidirectional"))
      (node (ref "R2") (pin "1") (pinfunction "1_1") (pintype "passive"))
      (node (ref "U7") (pin "46") (pinfunction "46_46") (pintype "bidirectional"))
    )
    (net (code "35") (name "ICE_LEDG") (class "Default")
      (node (ref "J9") (pin "9") (pinfunction "9_9") (pintype "bidirectional"))
      (node (ref "R3") (pin "1") (pinfunction "1_1") (pintype "passive"))
      (node (ref "U7") (pin "45") (pinfunction "45_45") (pintype "bidirectional"))
    )
    (net (code "36") (name "ICE_LEDR") (class "Default")
      (node (ref "J9") (pin "11") (pinfunction "11_11") (pintype "bidirectional"))
      (node (ref "R1") (pin "1") (pinfunction "1_1") (pintype "passive"))
      (node (ref "U7") (pin "44GBIN6") (pinfunction "44GBIN6_44GBIN6") (pintype "bidirectional"))
    )
    (net (code "37") (name "ICE_RGB0") (class "Default")
      (node (ref "J10") (pin "1") (pinfunction "1_1") (pintype "bidirectional"))
      (node (ref "U7") (pin "41RGB0") (pinfunction "41RGB0_41RGB0") (pintype "bidirectional"))
    )
    (net (code "38") (name "ICE_RGB1") (class "Default")
      (node (ref "J9") (pin "15") (pinfunction "15_15") (pintype "bidirectional"))
      (node (ref "U7") (pin "40RGB1") (pinfunction "40RGB1_40RGB1") (pintype "bidirectional"))
    )
    (net (code "39") (name "ICE_RGB2") (class "Default")
      (node (ref "J9") (pin "13") (pinfunction "13_13") (pintype "bidirectional"))
      (node (ref "U7") (pin "39RGB2") (pinfunction "39RGB2_39RGB2") (pintype "bidirectional"))
    )
    (net (code "40") (name "ICE_SCK") (class "Default")
      (node (ref "J14") (pin "3") (pinfunction "3_3") (pintype "bidirectional"))
      (node (ref "U10") (pin "6SCK") (pinfunction "6SCK_6SCK") (pintype "bidirectional"))
      (node (ref "U2") (pin "B2") (pinfunction "B2P017_B2") (pintype "bidirectional"))
      (node (ref "U7") (pin "15SPISCK") (pinfunction "15SPISCK_15SPISCK") (pintype "bidirectional"))
    )
    (net (code "41") (name "ICE_SDI") (class "Default")
      (node (ref "J14") (pin "1") (pinfunction "1_1") (pintype "bidirectional"))
      (node (ref "U10") (pin "5SIIO0") (pinfunction "5SIIO0_5SIIO0") (pintype "bidirectional"))
      (node (ref "U2") (pin "B4") (pinfunction "B4P015_B4") (pintype "bidirectional"))
      (node (ref "U7") (pin "14SPISO") (pinfunction "14SPISO_14SPISO") (pintype "bidirectional"))
    )
    (net (code "42") (name "ICE_SDO") (class "Default")
      (node (ref "J14") (pin "4") (pinfunction "4_4") (pintype "bidirectional"))
      (node (ref "U10") (pin "2SOIO1") (pinfunction "2SOIO1_2SOIO1") (pintype "bidirectional"))
      (node (ref "U2") (pin "B3") (pinfunction "B3P014_B3") (pintype "bidirectional"))
      (node (ref "U7") (pin "17SPISI") (pinfunction "17SPISI_17SPISI") (pintype "bidirectional"))
    )
    (net (code "43") (name "ICE_SSB") (class "Default")
      (node (ref "J14") (pin "2") (pinfunction "2_2") (pintype "bidirectional"))
      (node (ref "R37") (pin "2") (pinfunction "2_2") (pintype "passive"))
      (node (ref "U10") (pin "1CSN") (pinfunction "1CSN_1CSN") (pintype "bidirectional"))
      (node (ref "U2") (pin "B6") (pinfunction "B6P013_B6") (pintype "bidirectional"))
      (node (ref "U7") (pin "16SPISS") (pinfunction "16SPISS_16SPISS") (pintype "bidirectional"))
    )
    (net (code "44") (name "ICE_VCC") (class "Default")
      (node (ref "C67") (pin "1") (pinfunction "1_1") (pintype "passive"))
      (node (ref "C68") (pin "1") (pinfunction "1_1") (pintype "passive"))
      (node (ref "C69") (pin "1") (pinfunction "1_1") (pintype "passive"))
      (node (ref "C70") (pin "1") (pinfunction "1_1") (pintype "passive"))
      (node (ref "C71") (pin "1") (pinfunction "1_1") (pintype "passive"))
      (node (ref "R16") (pin "1") (pinfunction "1_1") (pintype "passive"))
      (node (ref "U7") (pin "30VCC") (pinfunction "30VCC_30VCC") (pintype "bidirectional"))
      (node (ref "U7") (pin "5VCC") (pinfunction "5VCC_5VCC") (pintype "bidirectional"))
    )
    (net (code "45") (name "ICE_VCCIO0") (class "Default")
      (node (ref "C65") (pin "1") (pinfunction "1_1") (pintype "passive"))
      (node (ref "R36") (pin "1") (pinfunction "1_1") (pintype "passive"))
      (node (ref "U7") (pin "33VCCIO0") (pinfunction "33VCCIO0_33VCCIO0") (pintype "bidirectional"))
    )
    (net (code "46") (name "ICE_VCCIO1") (class "Default")
      (node (ref "C63") (pin "1") (pinfunction "1_1") (pintype "passive"))
      (node (ref "R14") (pin "2") (pinfunction "2_2") (pintype "passive"))
      (node (ref "R35") (pin "1") (pinfunction "1_1") (pintype "passive"))
      (node (ref "R9") (pin "2") (pinfunction "2_2") (pintype "passive"))
      (node (ref "U7") (pin "22SPIVCCIO1") (pinfunction "22SPIVCCIO1_22SPIVCCIO1") (pintype "bidirectional"))
    )
    (net (code "47") (name "ICE_VCCIO2") (class "Default")
      (node (ref "C62") (pin "1") (pinfunction "1_1") (pintype "passive"))
      (node (ref "J4") (pin "2") (pinfunction "2_2") (pintype "bidirectional"))
      (node (ref "R15") (pin "2") (pinfunction "2_2") (pintype "passive"))
      (node (ref "U7") (pin "1VCCIO2") (pinfunction "1VCCIO2_1VCCIO2") (pintype "bidirectional"))
    )
    (net (code "48") (name "ICE_XTALEN") (class "Default")
      (node (ref "OSC1") (pin "1OESTN") (pinfunction "1OESTN_1OESTN") (pintype "bidirectional"))
      (node (ref "R13") (pin "1") (pinfunction "1_1") (pintype "passive"))
      (node (ref "R41") (pin "2") (pinfunction "2_2") (pintype "passive"))
      (node (ref "T13") (pin "1") (pinfunction "1_1") (pintype "bidirectional"))
    )
    (net (code "49") (name "JLINK_SWO") (class "Default")
      (node (ref "J1") (pin "6SWO") (pinfunction "6SWO_6SWO") (pintype "bidirectional"))
      (node (ref "T11") (pin "T") (pinfunction "T_T") (pintype "bidirectional"))
    )
    (net (code "50") (name "NRFICE1") (class "Default")
      (node (ref "J16") (pin "2") (pinfunction "2_2") (pintype "bidirectional"))
      (node (ref "U2") (pin "8") (pinfunction "8P003_8") (pintype "bidirectional"))
      (node (ref "U7") (pin "13") (pinfunction "13_13") (pintype "bidirectional"))
    )
    (net (code "51") (name "NRFICE2") (class "Default")
      (node (ref "J16") (pin "4") (pinfunction "4_4") (pintype "bidirectional"))
      (node (ref "U2") (pin "7") (pinfunction "7P002_7") (pintype "bidirectional"))
      (node (ref "U7") (pin "18") (pinfunction "18_18") (pintype "bidirectional"))
    )
    (net (code "52") (name "NRFICE4") (class "Default")
      (node (ref "J16") (pin "8") (pinfunction "8_8") (pintype "bidirectional"))
      (node (ref "U2") (pin "Z6") (pinfunction "Z6P115_Z6") (pintype "bidirectional"))
      (node (ref "U7") (pin "10") (pinfunction "10_10") (pintype "bidirectional"))
    )
    (net (code "53") (name "NRFICE5") (class "Default")
      (node (ref "J16") (pin "10") (pinfunction "10_10") (pintype "bidirectional"))
      (node (ref "U2") (pin "A5") (pinfunction "A5P100_A5") (pintype "bidirectional"))
      (node (ref "U7") (pin "11") (pinfunction "11_11") (pintype "bidirectional"))
    )
    (net (code "54") (name "NRFICE6") (class "Default")
      (node (ref "J16") (pin "12") (pinfunction "12_12") (pintype "bidirectional"))
      (node (ref "U2") (pin "Z5") (pinfunction "Z5P114_Z5") (pintype "bidirectional"))
      (node (ref "U7") (pin "12") (pinfunction "12_12") (pintype "bidirectional"))
    )
    (net (code "55") (name "NRFICE7") (class "Default")
      (node (ref "J16") (pin "14") (pinfunction "14_14") (pintype "bidirectional"))
      (node (ref "U2") (pin "Z4") (pinfunction "Z4P113_Z4") (pintype "bidirectional"))
      (node (ref "U7") (pin "25") (pinfunction "25_25") (pintype "bidirectional"))
    )
    (net (code "56") (name "NRFICE8") (class "Default")
      (node (ref "J16") (pin "16") (pinfunction "16_16") (pintype "bidirectional"))
      (node (ref "U2") (pin "Z3") (pinfunction "Z3P112_Z3") (pintype "bidirectional"))
      (node (ref "U7") (pin "26") (pinfunction "26_26") (pintype "bidirectional"))
    )
    (net (code "57") (name "NRFICE9") (class "Default")
      (node (ref "J10") (pin "2") (pinfunction "2_2") (pintype "bidirectional"))
      (node (ref "U2") (pin "Z2") (pinfunction "Z2P111_Z2") (pintype "bidirectional"))
      (node (ref "U7") (pin "27") (pinfunction "27_27") (pintype "bidirectional"))
    )
    (net (code "58") (name "NRFICE10") (class "Default")
      (node (ref "J10") (pin "3") (pinfunction "3_3") (pintype "bidirectional"))
      (node (ref "U2") (pin "Z1") (pinfunction "Z1P110_Z1") (pintype "bidirectional"))
      (node (ref "U7") (pin "28") (pinfunction "28_28") (pintype "bidirectional"))
    )
    (net (code "59") (name "NRFUSBSHLD") (class "Default")
      (node (ref "J2") (pin "S1") (pinfunction "S1_S1") (pintype "bidirectional"))
      (node (ref "J2") (pin "S2") (pinfunction "S2_S2") (pintype "bidirectional"))
      (node (ref "J2") (pin "S3") (pinfunction "S3_S3") (pintype "bidirectional"))
      (node (ref "J2") (pin "S4") (pinfunction "S4_S4") (pintype "bidirectional"))
      (node (ref "R27") (pin "2") (pinfunction "2_2") (pintype "passive"))
    )
    (net (code "60") (name "NRF_AIN0") (class "Default")
      (node (ref "J11") (pin "6") (pinfunction "6_6") (pintype "bidirectional"))
      (node (ref "U2") (pin "5") (pinfunction "5P004_5") (pintype "bidirectional"))
    )
    (net (code "61") (name "NRF_AIN1") (class "Default")
      (node (ref "J11") (pin "5") (pinfunction "5_5") (pintype "bidirectional"))
      (node (ref "U2") (pin "6") (pinfunction "6P005_6") (pintype "bidirectional"))
    )
    (net (code "62") (name "NRF_AIN2") (class "Default")
      (node (ref "J11") (pin "3") (pinfunction "3_3") (pintype "bidirectional"))
      (node (ref "U2") (pin "A1") (pinfunction "A1P006_A1") (pintype "bidirectional"))
    )
    (net (code "63") (name "NRF_AIN3") (class "Default")
      (node (ref "J11") (pin "4") (pinfunction "4_4") (pintype "bidirectional"))
      (node (ref "U2") (pin "A2") (pinfunction "A2P007_A2") (pintype "bidirectional"))
    )
    (net (code "64") (name "NRF_AIN4") (class "Default")
      (node (ref "J9") (pin "4") (pinfunction "4_4") (pintype "bidirectional"))
      (node (ref "U2") (pin "C6") (pinfunction "C6P025_C6") (pintype "bidirectional"))
    )
    (net (code "65") (name "NRF_AIN5") (class "Default")
      (node (ref "J11") (pin "1") (pinfunction "1_1") (pintype "bidirectional"))
      (node (ref "U2") (pin "D1") (pinfunction "D1P026_D1") (pintype "bidirectional"))
    )
    (net (code "66") (name "NRF_AIN6") (class "Default")
      (node (ref "J11") (pin "2") (pinfunction "2_2") (pintype "bidirectional"))
      (node (ref "U2") (pin "D2") (pinfunction "D2P027_D2") (pintype "bidirectional"))
    )
    (net (code "67") (name "NRF_AIN7") (class "Default")
      (node (ref "J9") (pin "2") (pinfunction "2_2") (pintype "bidirectional"))
      (node (ref "U2") (pin "D3") (pinfunction "D3P028_D3") (pintype "bidirectional"))
    )
    (net (code "68") (name "NRF_BTN") (class "Default")
      (node (ref "R8") (pin "1") (pinfunction "1_1") (pintype "passive"))
      (node (ref "U2") (pin "Z0") (pinfunction "Z0P109_Z0") (pintype "bidirectional"))
    )
    (net (code "69") (name "NRF_CTS") (class "Default")
      (node (ref "U2") (pin "E3") (pinfunction "E3P107_E3") (pintype "bidirectional"))
      (node (ref "U8") (pin "17PA7") (pinfunction "17PA7_17PA7") (pintype "bidirectional"))
    )
    (net (code "70") (name "NRF_DCOUT") (class "Default")
      (node (ref "T2") (pin "1") (pinfunction "1_1") (pintype "bidirectional"))
      (node (ref "U2") (pin "F5") (pinfunction "F5DCCH_F5") (pintype "bidirectional"))
    )
    (net (code "71") (name "NRF_LEDB") (class "Default")
      (node (ref "J3") (pin "1") (pinfunction "1_1") (pintype "bidirectional"))
      (node (ref "R5") (pin "1") (pinfunction "1_1") (pintype "passive"))
      (node (ref "U2") (pin "B1") (pinfunction "B1P019_B1") (pintype "bidirectional"))
    )
    (net (code "72") (name "NRF_LEDG") (class "Default")
      (node (ref "J3") (pin "2") (pinfunction "2_2") (pintype "bidirectional"))
      (node (ref "R6") (pin "1") (pinfunction "1_1") (pintype "passive"))
      (node (ref "U2") (pin "E0") (pinfunction "E0P104_E0") (pintype "bidirectional"))
    )
    (net (code "73") (name "NRF_LEDR") (class "Default")
      (node (ref "J3") (pin "3") (pinfunction "3_3") (pintype "bidirectional"))
      (node (ref "R7") (pin "1") (pinfunction "1_1") (pintype "passive"))
      (node (ref "U2") (pin "E1") (pinfunction "E1P105_E1") (pintype "bidirectional"))
    )
    (net (code "74") (name "NRF_RSTN") (class "Default")
      (node (ref "R17") (pin "1") (pinfunction "1_1") (pintype "passive"))
      (node (ref "R23") (pin "1") (pinfunction "1_1") (pintype "passive"))
      (node (ref "SW1") (pin "2") (pinfunction "2_2") (pintype "bidirectional"))
      (node (ref "U2") (pin "14") (pinfunction "14RESET_14") (pintype "bidirectional"))
      (node (ref "U8") (pin "11PA1") (pinfunction "11PA1_11PA1") (pintype "bidirectional"))
    )
    (net (code "75") (name "NRF_RTS") (class "Default")
      (node (ref "U2") (pin "13") (pinfunction "13P030_13") (pintype "bidirectional"))
      (node (ref "U8") (pin "16PA6") (pinfunction "16PA6_16PA6") (pintype "bidirectional"))
    )
    (net (code "76") (name "NRF_RXD") (class "Default")
      (node (ref "T19") (pin "T") (pinfunction "T_T") (pintype "bidirectional"))
      (node (ref "U2") (pin "D5") (pinfunction "D5P022_D5") (pintype "bidirectional"))
      (node (ref "U8") (pin "31PA10") (pinfunction "31PA10_31PA10") (pintype "bidirectional"))
    )
    (net (code "77") (name "NRF_SPIDCN") (class "Default")
      (node (ref "T3") (pin "1") (pinfunction "1_1") (pintype "bidirectional"))
      (node (ref "U2") (pin "12") (pinfunction "12P011_12") (pintype "bidirectional"))
    )
    (net (code "78") (name "NRF_SWDCLK") (class "Default")
      (node (ref "R11") (pin "1") (pinfunction "1_1") (pintype "passive"))
      (node (ref "T18") (pin "T") (pinfunction "T_T") (pintype "bidirectional"))
      (node (ref "U2") (pin "15") (pinfunction "15SWCLK_15") (pintype "bidirectional"))
    )
    (net (code "79") (name "NRF_SWDIO") (class "Default")
      (node (ref "T17") (pin "T") (pinfunction "T_T") (pintype "bidirectional"))
      (node (ref "U2") (pin "16") (pinfunction "16SWDIO_16") (pintype "bidirectional"))
      (node (ref "U8") (pin "14PA4") (pinfunction "14PA4_14PA4") (pintype "bidirectional"))
    )
    (net (code "80") (name "NRF_TXD") (class "Default")
      (node (ref "T20") (pin "T") (pinfunction "T_T") (pintype "bidirectional"))
      (node (ref "U2") (pin "D4") (pinfunction "D4P029_D4") (pintype "bidirectional"))
      (node (ref "U8") (pin "30PA9") (pinfunction "30PA9_30PA9") (pintype "bidirectional"))
    )
    (net (code "81") (name "NRF_USB5V") (class "Default")
      (node (ref "C32") (pin "1") (pinfunction "1_1") (pintype "passive"))
      (node (ref "J4") (pin "7") (pinfunction "7_7") (pintype "bidirectional"))
      (node (ref "L1") (pin "2") (pinfunction "2_2") (pintype "passive"))
      (node (ref "U2") (pin "F6") (pinfunction "F6VBUS_F6") (pintype "bidirectional"))
    )
    (net (code "82") (name "NRF_USBCC1") (class "Default")
      (node (ref "J2") (pin "A5") (pinfunction "A5_A5") (pintype "bidirectional"))
      (node (ref "R19") (pin "2") (pinfunction "2_2") (pintype "passive"))
    )
    (net (code "83") (name "NRF_USBCC2") (class "Default")
      (node (ref "J2") (pin "B5") (pinfunction "B5_B5") (pintype "bidirectional"))
      (node (ref "R20") (pin "2") (pinfunction "2_2") (pintype "passive"))
    )
    (net (code "84") (name "NRF_USBCON5V") (class "Default")
      (node (ref "C31") (pin "1") (pinfunction "1_1") (pintype "passive"))
      (node (ref "C34") (pin "1") (pinfunction "1_1") (pintype "passive"))
      (node (ref "C9") (pin "1") (pinfunction "1_1") (pintype "passive"))
      (node (ref "D2") (pin "4VCC") (pinfunction "4VCC_4VCC") (pintype "bidirectional"))
      (node (ref "J2") (pin "A4B9") (pinfunction "A4B9_A4B9") (pintype "bidirectional"))
      (node (ref "J2") (pin "B4A9") (pinfunction "B4A9_B4A9") (pintype "bidirectional"))
      (node (ref "L1") (pin "1") (pinfunction "1_1") (pintype "passive"))
      (node (ref "T10") (pin "1") (pinfunction "1_1") (pintype "bidirectional"))
      (node (ref "T24") (pin "T") (pinfunction "T_T") (pintype "bidirectional"))
    )
    (net (code "85") (name "NRF_USBDN") (class "Default")
      (node (ref "D2") (pin "3IO2") (pinfunction "3IO2_3IO2") (pintype "bidirectional"))
      (node (ref "J2") (pin "A7") (pinfunction "A7_A7") (pintype "bidirectional"))
      (node (ref "J2") (pin "B7") (pinfunction "B7_B7") (pintype "bidirectional"))
      (node (ref "T21") (pin "T") (pinfunction "T_T") (pintype "bidirectional"))
      (node (ref "U2") (pin "E5") (pinfunction "E5DN_E5") (pintype "bidirectional"))
    )
    (net (code "86") (name "NRF_USBDP") (class "Default")
      (node (ref "D2") (pin "2IO1") (pinfunction "2IO1_2IO1") (pintype "bidirectional"))
      (node (ref "J2") (pin "A6") (pinfunction "A6_A6") (pintype "bidirectional"))
      (node (ref "J2") (pin "B6") (pinfunction "B6_B6") (pintype "bidirectional"))
      (node (ref "T22") (pin "T") (pinfunction "T_T") (pintype "bidirectional"))
      (node (ref "U2") (pin "E4") (pinfunction "E4DP_E4") (pintype "bidirectional"))
    )
    (net (code "87") (name "NRF_USBSBU1") (class "Default")
      (node (ref "J2") (pin "A8") (pinfunction "A8_A8") (pintype "bidirectional"))
      (node (ref "T9") (pin "T") (pinfunction "T_T") (pintype "bidirectional"))
    )
    (net (code "88") (name "NRF_USBSBU2") (class "Default")
      (node (ref "J2") (pin "B8") (pinfunction "B8_B8") (pintype "bidirectional"))
      (node (ref "T8") (pin "T") (pinfunction "T_T") (pintype "bidirectional"))
    )
    (net (code "89") (name "NRF_VCC") (class "Default")
      (node (ref "C3") (pin "1") (pinfunction "1_1") (pintype "passive"))
      (node (ref "C48") (pin "1") (pinfunction "1_1") (pintype "passive"))
      (node (ref "R33") (pin "1") (pinfunction "1_1") (pintype "passive"))
      (node (ref "U2") (pin "9") (pinfunction "9VDD_9") (pintype "bidirectional"))
    )
    (net (code "90") (name "NRF_VDDH") (class "Default")
      (node (ref "T4") (pin "1") (pinfunction "1_1") (pintype "bidirectional"))
      (node (ref "U2") (pin "F4") (pinfunction "F4VDDH_F4") (pintype "bidirectional"))
    )
    (net (code "91") (name "Net-(C1-Pad1)") (class "Default")
      (node (ref "C1") (pin "1") (pinfunction "1_1") (pintype "passive"))
      (node (ref "J3") (pin "4") (pinfunction "4_4") (pintype "bidirectional"))
      (node (ref "R38") (pin "1") (pinfunction "1_1") (pintype "passive"))
      (node (ref "U5") (pin "4ANODE") (pinfunction "4ANODE_4ANODE") (pintype "bidirectional"))
    )
    (net (code "92") (name "Net-(C2-Pad1)") (class "Default")
      (node (ref "C2") (pin "1") (pinfunction "1_1") (pintype "passive"))
      (node (ref "R39") (pin "1") (pinfunction "1_1") (pintype "passive"))
      (node (ref "U1") (pin "4ANODE") (pinfunction "4ANODE_4ANODE") (pintype "bidirectional"))
    )
    (net (code "93") (name "Net-(C10-Pad1)") (class "Default")
      (node (ref "C10") (pin "1") (pinfunction "1_1") (pintype "passive"))
      (node (ref "OSC1") (pin "4VCC") (pinfunction "4VCC_4VCC") (pintype "bidirectional"))
      (node (ref "R12") (pin "1") (pinfunction "1_1") (pintype "passive"))
    )
    (net (code "94") (name "Net-(C19-Pad1)") (class "Default")
      (node (ref "C19") (pin "1") (pinfunction "1_1") (pintype "passive"))
      (node (ref "R18") (pin "1") (pinfunction "1_1") (pintype "passive"))
      (node (ref "R8") (pin "2") (pinfunction "2_2") (pintype "passive"))
      (node (ref "SW6") (pin "2") (pinfunction "2_2") (pintype "bidirectional"))
    )
    (net (code "95") (name "Net-(C20-Pad1)") (class "Default")
      (node (ref "C20") (pin "1") (pinfunction "1_1") (pintype "passive"))
      (node (ref "R15") (pin "1") (pinfunction "1_1") (pintype "passive"))
      (node (ref "R22") (pin "2") (pinfunction "2_2") (pintype "passive"))
      (node (ref "SW7") (pin "2") (pinfunction "2_2") (pintype "bidirectional"))
    )
    (net (code "96") (name "Net-(D5-PadC)") (class "Default")
      (node (ref "D5") (pin "C") (pinfunction "C_C") (pintype "passive"))
      (node (ref "R10") (pin "1") (pinfunction "1_1") (pintype "passive"))
    )
    (net (code "97") (name "Net-(R1-Pad2)") (class "Default")
      (node (ref "R1") (pin "2") (pinfunction "2_2") (pintype "passive"))
      (node (ref "U1") (pin "3RED") (pinfunction "3RED_3RED") (pintype "bidirectional"))
    )
    (net (code "98") (name "Net-(R2-Pad2)") (class "Default")
      (node (ref "R2") (pin "2") (pinfunction "2_2") (pintype "passive"))
      (node (ref "U1") (pin "1BLUE") (pinfunction "1BLUE_1BLUE") (pintype "bidirectional"))
    )
    (net (code "99") (name "Net-(R3-Pad2)") (class "Default")
      (node (ref "R3") (pin "2") (pinfunction "2_2") (pintype "passive"))
      (node (ref "U1") (pin "2GREEN") (pinfunction "2GREEN_2GREEN") (pintype "bidirectional"))
    )
    (net (code "100") (name "Net-(R5-Pad2)") (class "Default")
      (node (ref "R5") (pin "2") (pinfunction "2_2") (pintype "passive"))
      (node (ref "U5") (pin "1BLUE") (pinfunction "1BLUE_1BLUE") (pintype "bidirectional"))
    )
    (net (code "101") (name "Net-(R6-Pad2)") (class "Default")
      (node (ref "R6") (pin "2") (pinfunction "2_2") (pintype "passive"))
      (node (ref "U5") (pin "2GREEN") (pinfunction "2GREEN_2GREEN") (pintype "bidirectional"))
    )
    (net (code "102") (name "Net-(R7-Pad2)") (class "Default")
      (node (ref "R7") (pin "2") (pinfunction "2_2") (pintype "passive"))
      (node (ref "U5") (pin "3RED") (pinfunction "3RED_3RED") (pintype "bidirectional"))
    )
    (net (code "103") (name "Net-(R11-Pad2)") (class "Default")
      (node (ref "R11") (pin "2") (pinfunction "2_2") (pintype "passive"))
      (node (ref "U8") (pin "12PA2") (pinfunction "12PA2_12PA2") (pintype "bidirectional"))
    )
    (net (code "104") (name "Net-(R28-Pad2)") (class "Default")
      (node (ref "R28") (pin "2") (pinfunction "2_2") (pintype "passive"))
      (node (ref "SW1") (pin "S") (pinfunction "S_S") (pintype "bidirectional"))
    )
    (net (code "105") (name "Net-(R29-Pad2)") (class "Default")
      (node (ref "R29") (pin "2") (pinfunction "2_2") (pintype "passive"))
      (node (ref "SW6") (pin "S") (pinfunction "S_S") (pintype "bidirectional"))
    )
    (net (code "106") (name "Net-(R30-Pad2)") (class "Default")
      (node (ref "R30") (pin "2") (pinfunction "2_2") (pintype "passive"))
      (node (ref "SW8") (pin "S") (pinfunction "S_S") (pintype "bidirectional"))
    )
    (net (code "107") (name "Net-(R31-Pad2)") (class "Default")
      (node (ref "R31") (pin "2") (pinfunction "2_2") (pintype "passive"))
      (node (ref "SW7") (pin "S") (pinfunction "S_S") (pintype "bidirectional"))
    )
    (net (code "108") (name "OBLED") (class "Default")
      (node (ref "R10") (pin "2") (pinfunction "2_2") (pintype "passive"))
      (node (ref "U8") (pin "10PA0") (pinfunction "10PA0_10PA0") (pintype "bidirectional"))
    )
    (net (code "109") (name "P0XL1") (class "Default")
      (node (ref "R40") (pin "1") (pinfunction "1_1") (pintype "passive"))
      (node (ref "U2") (pin "3") (pinfunction "3P000_3") (pintype "bidirectional"))
    )
    (net (code "110") (name "P1XL2") (class "Default")
      (node (ref "R40") (pin "2") (pinfunction "2_2") (pintype "passive"))
      (node (ref "U2") (pin "4") (pinfunction "4P001_4") (pintype "bidirectional"))
    )
    (net (code "111") (name "PLLVCC") (class "Default")
      (node (ref "C4") (pin "1") (pinfunction "1_1") (pintype "passive"))
      (node (ref "C75") (pin "1") (pinfunction "1_1") (pintype "passive"))
      (node (ref "R91") (pin "1") (pinfunction "1_1") (pintype "passive"))
      (node (ref "U7") (pin "29VCCPLL") (pinfunction "29VCCPLL_29VCCPLL") (pintype "bidirectional"))
    )
    (net (code "112") (name "STMUSBSHLD") (class "Default")
      (node (ref "J8") (pin "S1") (pinfunction "S1_S1") (pintype "bidirectional"))
      (node (ref "J8") (pin "S2") (pinfunction "S2_S2") (pintype "bidirectional"))
      (node (ref "J8") (pin "S3") (pinfunction "S3_S3") (pintype "bidirectional"))
      (node (ref "J8") (pin "S4") (pinfunction "S4_S4") (pintype "bidirectional"))
      (node (ref "R26") (pin "2") (pinfunction "2_2") (pintype "passive"))
    )
    (net (code "113") (name "STM_D_N") (class "Default")
      (node (ref "J8") (pin "A7") (pinfunction "A7_A7") (pintype "bidirectional"))
      (node (ref "J8") (pin "B7") (pinfunction "B7_B7") (pintype "bidirectional"))
      (node (ref "U8") (pin "32PA11") (pinfunction "32PA11_32PA11") (pintype "bidirectional"))
    )
    (net (code "114") (name "STM_D_P") (class "Default")
      (node (ref "J8") (pin "A6") (pinfunction "A6_A6") (pintype "bidirectional"))
      (node (ref "J8") (pin "B6") (pinfunction "B6_B6") (pintype "bidirectional"))
      (node (ref "U8") (pin "33PA12") (pinfunction "33PA12_33PA12") (pintype "bidirectional"))
    )
    (net (code "115") (name "STM_RESETN") (class "Default")
      (node (ref "J1") (pin "3NRESET") (pinfunction "3NRESET_3NRESET") (pintype "bidirectional"))
      (node (ref "U8") (pin "7NRST") (pinfunction "7NRST_7NRST") (pintype "bidirectional"))
    )
    (net (code "116") (name "STM_SWCLK") (class "Default")
      (node (ref "J1") (pin "4SWCLK") (pinfunction "4SWCLK_4SWCLK") (pintype "bidirectional"))
      (node (ref "T27") (pin "T") (pinfunction "T_T") (pintype "bidirectional"))
      (node (ref "U8") (pin "37PA14SWDCLK") (pinfunction "37PA14SWDCLK_37PA14SWDCLK") (pintype "bidirectional"))
    )
    (net (code "117") (name "STM_SWDIO") (class "Default")
      (node (ref "J1") (pin "2SWDIO") (pinfunction "2SWDIO_2SWDIO") (pintype "bidirectional"))
      (node (ref "T14") (pin "T") (pinfunction "T_T") (pintype "bidirectional"))
      (node (ref "U8") (pin "34PA13SWDIO") (pinfunction "34PA13SWDIO_34PA13SWDIO") (pintype "bidirectional"))
    )
    (net (code "118") (name "STM_SWO") (class "Default")
      (node (ref "T12") (pin "T") (pinfunction "T_T") (pintype "bidirectional"))
      (node (ref "U8") (pin "13PA3") (pinfunction "13PA3_13PA3") (pintype "bidirectional"))
    )
    (net (code "119") (name "STM_USB5V") (class "Default")
      (node (ref "J4") (pin "5") (pinfunction "5_5") (pintype "bidirectional"))
      (node (ref "J8") (pin "A4B9") (pinfunction "A4B9_A4B9") (pintype "bidirectional"))
      (node (ref "J8") (pin "B4A9") (pinfunction "B4A9_B4A9") (pintype "bidirectional"))
      (node (ref "T5") (pin "1") (pinfunction "1_1") (pintype "bidirectional"))
    )
    (net (code "120") (name "STM_USBCC1") (class "Default")
      (node (ref "J8") (pin "A5") (pinfunction "A5_A5") (pintype "bidirectional"))
      (node (ref "R25") (pin "2") (pinfunction "2_2") (pintype "passive"))
    )
    (net (code "121") (name "STM_USBCC2") (class "Default")
      (node (ref "J8") (pin "B5") (pinfunction "B5_B5") (pintype "bidirectional"))
      (node (ref "R21") (pin "2") (pinfunction "2_2") (pintype "passive"))
    )
    (net (code "122") (name "STM_USBSBU1") (class "Default")
      (node (ref "J8") (pin "A8") (pinfunction "A8_A8") (pintype "bidirectional"))
      (node (ref "T7") (pin "T") (pinfunction "T_T") (pintype "bidirectional"))
    )
    (net (code "123") (name "STM_USBSBU2") (class "Default")
      (node (ref "J8") (pin "B8") (pinfunction "B8_B8") (pintype "bidirectional"))
      (node (ref "T6") (pin "T") (pinfunction "T_T") (pintype "bidirectional"))
    )
    (net (code "124") (name "UARTRX") (class "Default")
      (node (ref "J9") (pin "16") (pinfunction "16_16") (pintype "bidirectional"))
      (node (ref "U2") (pin "C5") (pinfunction "C5P020_C5") (pintype "bidirectional"))
      (node (ref "U7") (pin "37GBIN1") (pinfunction "37GBIN1_37GBIN1") (pintype "bidirectional"))
    )
    (net (code "125") (name "UARTTX") (class "Default")
      (node (ref "J9") (pin "14") (pinfunction "14_14") (pintype "bidirectional"))
      (node (ref "U2") (pin "C4") (pinfunction "C4P023_C4") (pintype "bidirectional"))
      (node (ref "U7") (pin "36") (pinfunction "36_36") (pintype "bidirectional"))
    )
    (net (code "126") (name "VUSB") (class "Default")
      (node (ref "J4") (pin "10") (pinfunction "10_10") (pintype "bidirectional"))
      (node (ref "J4") (pin "6") (pinfunction "6_6") (pintype "bidirectional"))
    )
    (net (code "127") (name "unconnected-(J16-Pad1)") (class "Default")
      (node (ref "J16") (pin "1") (pinfunction "1_1") (pintype "bidirectional"))
    )
    (net (code "128") (name "unconnected-(U8-Pad2PC13)") (class "Default")
      (node (ref "U8") (pin "2PC13") (pinfunction "2PC13_2PC13") (pintype "bidirectional"))
    )
    (net (code "129") (name "unconnected-(U8-Pad3PC14OSC32IN)") (class "Default")
      (node (ref "U8") (pin "3PC14OSC32IN") (pinfunction "3PC14OSC32IN_3PC14OSC32IN") (pintype "bidirectional"))
    )
    (net (code "130") (name "unconnected-(U8-Pad4PC15OSC32OUT)") (class "Default")
      (node (ref "U8") (pin "4PC15OSC32OUT") (pinfunction "4PC15OSC32OUT_4PC15OSC32OUT") (pintype "bidirectional"))
    )
    (net (code "131") (name "unconnected-(U8-Pad5PF0OSCIN)") (class "Default")
      (node (ref "U8") (pin "5PF0OSCIN") (pinfunction "5PF0OSCIN_5PF0OSCIN") (pintype "bidirectional"))
    )
    (net (code "132") (name "unconnected-(U8-Pad6PF1OSCOUT)") (class "Default")
      (node (ref "U8") (pin "6PF1OSCOUT") (pinfunction "6PF1OSCOUT_6PF1OSCOUT") (pintype "bidirectional"))
    )
    (net (code "133") (name "unconnected-(U8-Pad15PA5)") (class "Default")
      (node (ref "U8") (pin "15PA5") (pinfunction "15PA5_15PA5") (pintype "bidirectional"))
    )
    (net (code "134") (name "unconnected-(U8-Pad18PB0)") (class "Default")
      (node (ref "U8") (pin "18PB0") (pinfunction "18PB0_18PB0") (pintype "bidirectional"))
    )
    (net (code "135") (name "unconnected-(U8-Pad19PB1)") (class "Default")
      (node (ref "U8") (pin "19PB1") (pinfunction "19PB1_19PB1") (pintype "bidirectional"))
    )
    (net (code "136") (name "unconnected-(U8-Pad20PB2)") (class "Default")
      (node (ref "U8") (pin "20PB2") (pinfunction "20PB2_20PB2") (pintype "bidirectional"))
    )
    (net (code "137") (name "unconnected-(U8-Pad21PB10)") (class "Default")
      (node (ref "U8") (pin "21PB10") (pinfunction "21PB10_21PB10") (pintype "bidirectional"))
    )
    (net (code "138") (name "unconnected-(U8-Pad22PB11)") (class "Default")
      (node (ref "U8") (pin "22PB11") (pinfunction "22PB11_22PB11") (pintype "bidirectional"))
    )
    (net (code "139") (name "unconnected-(U8-Pad25PB12)") (class "Default")
      (node (ref "U8") (pin "25PB12") (pinfunction "25PB12_25PB12") (pintype "bidirectional"))
    )
    (net (code "140") (name "unconnected-(U8-Pad26PB13)") (class "Default")
      (node (ref "U8") (pin "26PB13") (pinfunction "26PB13_26PB13") (pintype "bidirectional"))
    )
    (net (code "141") (name "unconnected-(U8-Pad27PB14)") (class "Default")
      (node (ref "U8") (pin "27PB14") (pinfunction "27PB14_27PB14") (pintype "bidirectional"))
    )
    (net (code "142") (name "unconnected-(U8-Pad28PB15)") (class "Default")
      (node (ref "U8") (pin "28PB15") (pinfunction "28PB15_28PB15") (pintype "bidirectional"))
    )
    (net (code "143") (name "unconnected-(U8-Pad29PA8)") (class "Default")
      (node (ref "U8") (pin "29PA8") (pinfunction "29PA8_29PA8") (pintype "bidirectional"))
    )
    (net (code "144") (name "unconnected-(U8-Pad38PA15)") (class "Default")
      (node (ref "U8") (pin "38PA15") (pinfunction "38PA15_38PA15") (pintype "bidirectional"))
    )
    (net (code "145") (name "unconnected-(U8-Pad39PB3)") (class "Default")
      (node (ref "U8") (pin "39PB3") (pinfunction "39PB3_39PB3") (pintype "bidirectional"))
    )
    (net (code "146") (name "unconnected-(U8-Pad40PB4)") (class "Default")
      (node (ref "U8") (pin "40PB4") (pinfunction "40PB4_40PB4") (pintype "bidirectional"))
    )
    (net (code "147") (name "unconnected-(U8-Pad41PB5)") (class "Default")
      (node (ref "U8") (pin "41PB5") (pinfunction "41PB5_41PB5") (pintype "bidirectional"))
    )
    (net (code "148") (name "unconnected-(U8-Pad42PB6)") (class "Default")
      (node (ref "U8") (pin "42PB6") (pinfunction "42PB6_42PB6") (pintype "bidirectional"))
    )
    (net (code "149") (name "unconnected-(U8-Pad43PB7)") (class "Default")
      (node (ref "U8") (pin "43PB7") (pinfunction "43PB7_43PB7") (pintype "bidirectional"))
    )
    (net (code "150") (name "unconnected-(U8-Pad45PB8)") (class "Default")
      (node (ref "U8") (pin "45PB8") (pinfunction "45PB8_45PB8") (pintype "bidirectional"))
    )
    (net (code "151") (name "unconnected-(U8-Pad46PB9)") (class "Default")
      (node (ref "U8") (pin "46PB9") (pinfunction "46PB9_46PB9") (pintype "bidirectional"))
    )
  )
)
